# design.net
KiCad netlist of a schematic drawn in EasyEDA Pro
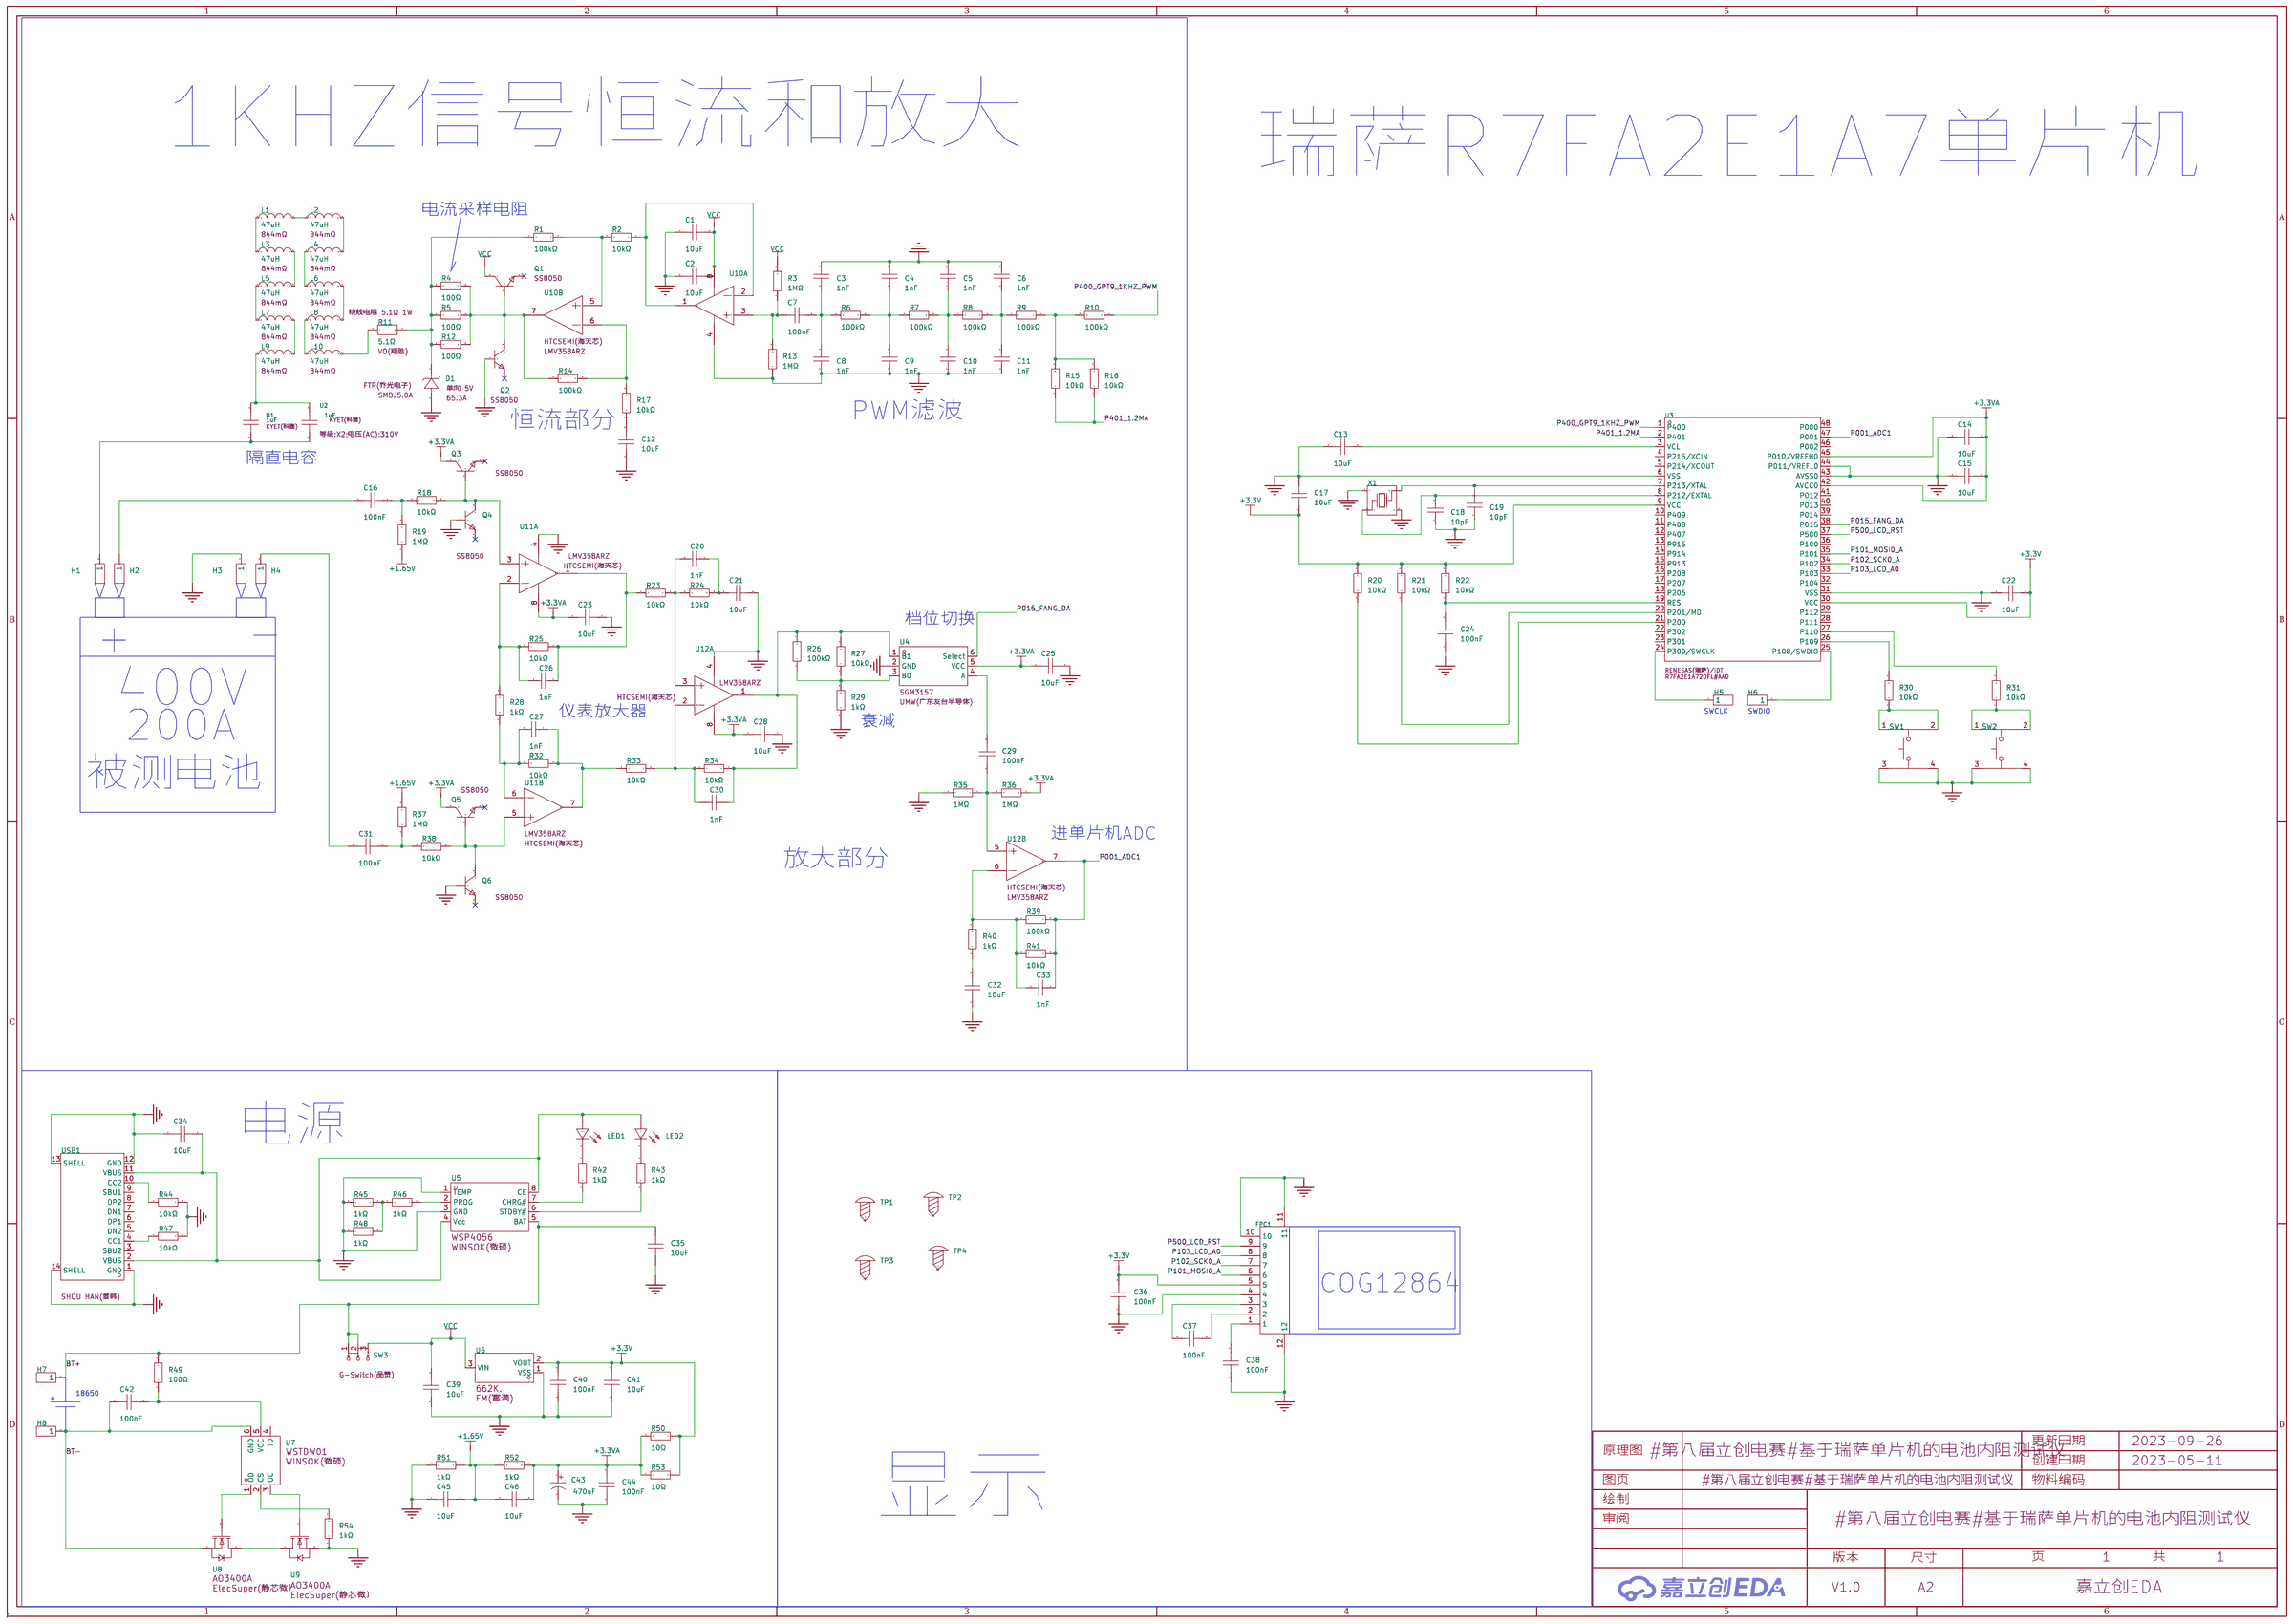
[diagram p0: schematic sheet]

(export (version "E")
  (design (tool "Eeschema 10.0.6"))
  (components
    (comp (ref "C1")
      (value "10uF")
      (footprint "easyedapro:C0603")
      (description "容值:10uF;精度:±10%;额定电压:10V;材质(温度系数):X5R;")
      (fields
        (field (name "Manufacturer Part") "CL10A106KP8NNNC")
        (field (name "Manufacturer") "SAMSUNG(三星)")
      )
      (libsource (lib "easyedapro") (part "CL10A106KP8NNNC"))
    )
    (comp (ref "C2")
      (value "10uF")
      (footprint "easyedapro:C0603")
      (description "容值:10uF;精度:±10%;额定电压:10V;材质(温度系数):X5R;")
      (fields
        (field (name "Manufacturer Part") "CL10A106KP8NNNC")
        (field (name "Manufacturer") "SAMSUNG(三星)")
      )
      (libsource (lib "easyedapro") (part "CL10A106KP8NNNC"))
    )
    (comp (ref "C3")
      (value "1nF")
      (footprint "easyedapro:C0603")
      (description "容值:1nF;精度:±5%;额定电压:50V;材质(温度系数):NP0;")
      (fields
        (field (name "Manufacturer Part") "CC0603JRNPO9BN102")
        (field (name "Manufacturer") "YAGEO(国巨)")
      )
      (libsource (lib "easyedapro") (part "CC0603JRNPO9BN102"))
    )
    (comp (ref "C4")
      (value "1nF")
      (footprint "easyedapro:C0603")
      (description "容值:1nF;精度:±5%;额定电压:50V;材质(温度系数):NP0;")
      (fields
        (field (name "Manufacturer Part") "CC0603JRNPO9BN102")
        (field (name "Manufacturer") "YAGEO(国巨)")
      )
      (libsource (lib "easyedapro") (part "CC0603JRNPO9BN102"))
    )
    (comp (ref "C5")
      (value "1nF")
      (footprint "easyedapro:C0603")
      (description "容值:1nF;精度:±5%;额定电压:50V;材质(温度系数):NP0;")
      (fields
        (field (name "Manufacturer Part") "CC0603JRNPO9BN102")
        (field (name "Manufacturer") "YAGEO(国巨)")
      )
      (libsource (lib "easyedapro") (part "CC0603JRNPO9BN102"))
    )
    (comp (ref "C6")
      (value "1nF")
      (footprint "easyedapro:C0603")
      (description "容值:1nF;精度:±5%;额定电压:50V;材质(温度系数):NP0;")
      (fields
        (field (name "Manufacturer Part") "CC0603JRNPO9BN102")
        (field (name "Manufacturer") "YAGEO(国巨)")
      )
      (libsource (lib "easyedapro") (part "CC0603JRNPO9BN102"))
    )
    (comp (ref "C7")
      (value "100nF")
      (footprint "easyedapro:C0603")
      (description "容值:100nF;精度:±10%;额定电压:50V;材质(温度系数):X7R;")
      (fields
        (field (name "Manufacturer Part") "CC0603KRX7R9BB104")
        (field (name "Manufacturer") "YAGEO(国巨)")
      )
      (libsource (lib "easyedapro") (part "CC0603KRX7R9BB104"))
    )
    (comp (ref "C8")
      (value "1nF")
      (footprint "easyedapro:C0603")
      (description "容值:1nF;精度:±5%;额定电压:50V;材质(温度系数):NP0;")
      (fields
        (field (name "Manufacturer Part") "CC0603JRNPO9BN102")
        (field (name "Manufacturer") "YAGEO(国巨)")
      )
      (libsource (lib "easyedapro") (part "CC0603JRNPO9BN102"))
    )
    (comp (ref "C9")
      (value "1nF")
      (footprint "easyedapro:C0603")
      (description "容值:1nF;精度:±5%;额定电压:50V;材质(温度系数):NP0;")
      (fields
        (field (name "Manufacturer Part") "CC0603JRNPO9BN102")
        (field (name "Manufacturer") "YAGEO(国巨)")
      )
      (libsource (lib "easyedapro") (part "CC0603JRNPO9BN102"))
    )
    (comp (ref "C10")
      (value "1nF")
      (footprint "easyedapro:C0603")
      (description "容值:1nF;精度:±5%;额定电压:50V;材质(温度系数):NP0;")
      (fields
        (field (name "Manufacturer Part") "CC0603JRNPO9BN102")
        (field (name "Manufacturer") "YAGEO(国巨)")
      )
      (libsource (lib "easyedapro") (part "CC0603JRNPO9BN102"))
    )
    (comp (ref "C11")
      (value "1nF")
      (footprint "easyedapro:C0603")
      (description "容值:1nF;精度:±5%;额定电压:50V;材质(温度系数):NP0;")
      (fields
        (field (name "Manufacturer Part") "CC0603JRNPO9BN102")
        (field (name "Manufacturer") "YAGEO(国巨)")
      )
      (libsource (lib "easyedapro") (part "CC0603JRNPO9BN102"))
    )
    (comp (ref "C12")
      (value "10uF")
      (footprint "easyedapro:C0603")
      (description "容值:10uF;精度:±10%;额定电压:10V;材质(温度系数):X5R;")
      (fields
        (field (name "Manufacturer Part") "CL10A106KP8NNNC")
        (field (name "Manufacturer") "SAMSUNG(三星)")
      )
      (libsource (lib "easyedapro") (part "CL10A106KP8NNNC"))
    )
    (comp (ref "C13")
      (value "10uF")
      (footprint "easyedapro:C0603")
      (description "容值:10uF;精度:±10%;额定电压:10V;材质(温度系数):X5R;")
      (fields
        (field (name "Manufacturer Part") "CL10A106KP8NNNC")
        (field (name "Manufacturer") "SAMSUNG(三星)")
      )
      (libsource (lib "easyedapro") (part "CL10A106KP8NNNC"))
    )
    (comp (ref "C14")
      (value "10uF")
      (footprint "easyedapro:C0603")
      (description "容值:10uF;精度:±10%;额定电压:10V;材质(温度系数):X5R;")
      (fields
        (field (name "Manufacturer Part") "CL10A106KP8NNNC")
        (field (name "Manufacturer") "SAMSUNG(三星)")
      )
      (libsource (lib "easyedapro") (part "CL10A106KP8NNNC"))
    )
    (comp (ref "C15")
      (value "10uF")
      (footprint "easyedapro:C0603")
      (description "容值:10uF;精度:±10%;额定电压:10V;材质(温度系数):X5R;")
      (fields
        (field (name "Manufacturer Part") "CL10A106KP8NNNC")
        (field (name "Manufacturer") "SAMSUNG(三星)")
      )
      (libsource (lib "easyedapro") (part "CL10A106KP8NNNC"))
    )
    (comp (ref "C16")
      (value "100nF")
      (footprint "easyedapro:CAP-TH_L13.0-W6.0-P10.00-D1.0")
      (description "等级:X2;容值:100nF;精度:±10%;")
      (fields (field (name "Manufacturer Part") "MP2104K27C3X6LC") (field (name "Manufacturer") "SRD(圣融达)"))
      (libsource (lib "easyedapro") (part "MP2104KGC3XLC"))
    )
    (comp (ref "C17")
      (value "10uF")
      (footprint "easyedapro:C0603")
      (description "容值:10uF;精度:±10%;额定电压:10V;材质(温度系数):X5R;")
      (fields
        (field (name "Manufacturer Part") "CL10A106KP8NNNC")
        (field (name "Manufacturer") "SAMSUNG(三星)")
      )
      (libsource (lib "easyedapro") (part "CL10A106KP8NNNC"))
    )
    (comp (ref "C18")
      (value "10pF")
      (footprint "easyedapro:C0603")
      (description "容值:10pF;精度:±5%;额定电压:50V;材质(温度系数):NP0;")
      (fields
        (field (name "Manufacturer Part") "CC0603JRNPO9BN100")
        (field (name "Manufacturer") "YAGEO(国巨)")
      )
      (libsource (lib "easyedapro") (part "CC0603JRNPO9BN100"))
    )
    (comp (ref "C19")
      (value "10pF")
      (footprint "easyedapro:C0603")
      (description "容值:10pF;精度:±5%;额定电压:50V;材质(温度系数):NP0;")
      (fields
        (field (name "Manufacturer Part") "CC0603JRNPO9BN100")
        (field (name "Manufacturer") "YAGEO(国巨)")
      )
      (libsource (lib "easyedapro") (part "CC0603JRNPO9BN100"))
    )
    (comp (ref "C20")
      (value "1nF")
      (footprint "easyedapro:C0603")
      (description "容值:1nF;精度:±5%;额定电压:50V;材质(温度系数):NP0;")
      (fields
        (field (name "Manufacturer Part") "CC0603JRNPO9BN102")
        (field (name "Manufacturer") "YAGEO(国巨)")
      )
      (libsource (lib "easyedapro") (part "CC0603JRNPO9BN102"))
    )
    (comp (ref "C21")
      (value "10uF")
      (footprint "easyedapro:C0603")
      (description "容值:10uF;精度:±10%;额定电压:10V;材质(温度系数):X5R;")
      (fields
        (field (name "Manufacturer Part") "CL10A106KP8NNNC")
        (field (name "Manufacturer") "SAMSUNG(三星)")
      )
      (libsource (lib "easyedapro") (part "CL10A106KP8NNNC"))
    )
    (comp (ref "C22")
      (value "10uF")
      (footprint "easyedapro:C0603")
      (description "容值:10uF;精度:±10%;额定电压:10V;材质(温度系数):X5R;")
      (fields
        (field (name "Manufacturer Part") "CL10A106KP8NNNC")
        (field (name "Manufacturer") "SAMSUNG(三星)")
      )
      (libsource (lib "easyedapro") (part "CL10A106KP8NNNC"))
    )
    (comp (ref "C23")
      (value "10uF")
      (footprint "easyedapro:C0603")
      (description "容值:10uF;精度:±10%;额定电压:10V;材质(温度系数):X5R;")
      (fields
        (field (name "Manufacturer Part") "CL10A106KP8NNNC")
        (field (name "Manufacturer") "SAMSUNG(三星)")
      )
      (libsource (lib "easyedapro") (part "CL10A106KP8NNNC"))
    )
    (comp (ref "C24")
      (value "100nF")
      (footprint "easyedapro:C0603")
      (description "容值:100nF;精度:±10%;额定电压:50V;材质(温度系数):X7R;")
      (fields
        (field (name "Manufacturer Part") "CC0603KRX7R9BB104")
        (field (name "Manufacturer") "YAGEO(国巨)")
      )
      (libsource (lib "easyedapro") (part "CC0603KRX7R9BB104"))
    )
    (comp (ref "C25")
      (value "10uF")
      (footprint "easyedapro:C0603")
      (description "容值:10uF;精度:±10%;额定电压:10V;材质(温度系数):X5R;")
      (fields
        (field (name "Manufacturer Part") "CL10A106KP8NNNC")
        (field (name "Manufacturer") "SAMSUNG(三星)")
      )
      (libsource (lib "easyedapro") (part "CL10A106KP8NNNC"))
    )
    (comp (ref "C26")
      (value "1nF")
      (footprint "easyedapro:C0603")
      (description "容值:1nF;精度:±5%;额定电压:50V;材质(温度系数):NP0;")
      (fields
        (field (name "Manufacturer Part") "CC0603JRNPO9BN102")
        (field (name "Manufacturer") "YAGEO(国巨)")
      )
      (libsource (lib "easyedapro") (part "CC0603JRNPO9BN102"))
    )
    (comp (ref "C27")
      (value "1nF")
      (footprint "easyedapro:C0603")
      (description "容值:1nF;精度:±5%;额定电压:50V;材质(温度系数):NP0;")
      (fields
        (field (name "Manufacturer Part") "CC0603JRNPO9BN102")
        (field (name "Manufacturer") "YAGEO(国巨)")
      )
      (libsource (lib "easyedapro") (part "CC0603JRNPO9BN102"))
    )
    (comp (ref "C28")
      (value "10uF")
      (footprint "easyedapro:C0603")
      (description "容值:10uF;精度:±10%;额定电压:10V;材质(温度系数):X5R;")
      (fields
        (field (name "Manufacturer Part") "CL10A106KP8NNNC")
        (field (name "Manufacturer") "SAMSUNG(三星)")
      )
      (libsource (lib "easyedapro") (part "CL10A106KP8NNNC"))
    )
    (comp (ref "C29")
      (value "100nF")
      (footprint "easyedapro:C0603")
      (description "容值:100nF;精度:±10%;额定电压:50V;材质(温度系数):X7R;")
      (fields
        (field (name "Manufacturer Part") "CC0603KRX7R9BB104")
        (field (name "Manufacturer") "YAGEO(国巨)")
      )
      (libsource (lib "easyedapro") (part "CC0603KRX7R9BB104"))
    )
    (comp (ref "C30")
      (value "1nF")
      (footprint "easyedapro:C0603")
      (description "容值:1nF;精度:±5%;额定电压:50V;材质(温度系数):NP0;")
      (fields
        (field (name "Manufacturer Part") "CC0603JRNPO9BN102")
        (field (name "Manufacturer") "YAGEO(国巨)")
      )
      (libsource (lib "easyedapro") (part "CC0603JRNPO9BN102"))
    )
    (comp (ref "C31")
      (value "100nF")
      (footprint "easyedapro:CAP-TH_L13.0-W6.0-P10.00-D1.0")
      (description "等级:X2;容值:100nF;精度:±10%;")
      (fields (field (name "Manufacturer Part") "MP2104K27C3X6LC") (field (name "Manufacturer") "SRD(圣融达)"))
      (libsource (lib "easyedapro") (part "MP2104KGC3XLC"))
    )
    (comp (ref "C32")
      (value "10uF")
      (footprint "easyedapro:C0603")
      (description "容值:10uF;精度:±10%;额定电压:10V;材质(温度系数):X5R;")
      (fields
        (field (name "Manufacturer Part") "CL10A106KP8NNNC")
        (field (name "Manufacturer") "SAMSUNG(三星)")
      )
      (libsource (lib "easyedapro") (part "CL10A106KP8NNNC"))
    )
    (comp (ref "C33")
      (value "1nF")
      (footprint "easyedapro:C0603")
      (description "容值:1nF;精度:±5%;额定电压:50V;材质(温度系数):NP0;")
      (fields
        (field (name "Manufacturer Part") "CC0603JRNPO9BN102")
        (field (name "Manufacturer") "YAGEO(国巨)")
      )
      (libsource (lib "easyedapro") (part "CC0603JRNPO9BN102"))
    )
    (comp (ref "C34")
      (value "10uF")
      (footprint "easyedapro:C0603")
      (description "容值:10uF;精度:±10%;额定电压:10V;材质(温度系数):X5R;")
      (fields
        (field (name "Manufacturer Part") "CL10A106KP8NNNC")
        (field (name "Manufacturer") "SAMSUNG(三星)")
      )
      (libsource (lib "easyedapro") (part "CL10A106KP8NNNC"))
    )
    (comp (ref "C35")
      (value "10uF")
      (footprint "easyedapro:C0603")
      (description "容值:10uF;精度:±10%;额定电压:10V;材质(温度系数):X5R;")
      (fields
        (field (name "Manufacturer Part") "CL10A106KP8NNNC")
        (field (name "Manufacturer") "SAMSUNG(三星)")
      )
      (libsource (lib "easyedapro") (part "CL10A106KP8NNNC"))
    )
    (comp (ref "C36")
      (value "100nF")
      (footprint "easyedapro:C0603")
      (description "容值:100nF;精度:±10%;额定电压:50V;材质(温度系数):X7R;")
      (fields
        (field (name "Manufacturer Part") "CC0603KRX7R9BB104")
        (field (name "Manufacturer") "YAGEO(国巨)")
      )
      (libsource (lib "easyedapro") (part "CC0603KRX7R9BB104"))
    )
    (comp (ref "C37")
      (value "100nF")
      (footprint "easyedapro:C0603")
      (description "容值:100nF;精度:±10%;额定电压:50V;材质(温度系数):X7R;")
      (fields
        (field (name "Manufacturer Part") "CC0603KRX7R9BB104")
        (field (name "Manufacturer") "YAGEO(国巨)")
      )
      (libsource (lib "easyedapro") (part "CC0603KRX7R9BB104"))
    )
    (comp (ref "C38")
      (value "100nF")
      (footprint "easyedapro:C0603")
      (description "容值:100nF;精度:±10%;额定电压:50V;材质(温度系数):X7R;")
      (fields
        (field (name "Manufacturer Part") "CC0603KRX7R9BB104")
        (field (name "Manufacturer") "YAGEO(国巨)")
      )
      (libsource (lib "easyedapro") (part "CC0603KRX7R9BB104"))
    )
    (comp (ref "C39")
      (value "10uF")
      (footprint "easyedapro:C0603")
      (description "容值:10uF;精度:±10%;额定电压:10V;材质(温度系数):X5R;")
      (fields
        (field (name "Manufacturer Part") "CL10A106KP8NNNC")
        (field (name "Manufacturer") "SAMSUNG(三星)")
      )
      (libsource (lib "easyedapro") (part "CL10A106KP8NNNC"))
    )
    (comp (ref "C40")
      (value "100nF")
      (footprint "easyedapro:C0603")
      (description "容值:100nF;精度:±10%;额定电压:50V;材质(温度系数):X7R;")
      (fields
        (field (name "Manufacturer Part") "CC0603KRX7R9BB104")
        (field (name "Manufacturer") "YAGEO(国巨)")
      )
      (libsource (lib "easyedapro") (part "CC0603KRX7R9BB104"))
    )
    (comp (ref "C41")
      (value "10uF")
      (footprint "easyedapro:C0603")
      (description "容值:10uF;精度:±10%;额定电压:10V;材质(温度系数):X5R;")
      (fields
        (field (name "Manufacturer Part") "CL10A106KP8NNNC")
        (field (name "Manufacturer") "SAMSUNG(三星)")
      )
      (libsource (lib "easyedapro") (part "CL10A106KP8NNNC"))
    )
    (comp (ref "C42")
      (value "100nF")
      (footprint "easyedapro:C0603")
      (description "容值:100nF;精度:±10%;额定电压:50V;材质(温度系数):X7R;")
      (fields
        (field (name "Manufacturer Part") "CC0603KRX7R9BB104")
        (field (name "Manufacturer") "YAGEO(国巨)")
      )
      (libsource (lib "easyedapro") (part "CC0603KRX7R9BB104"))
    )
    (comp (ref "C43")
      (value "470uF")
      (footprint "easyedapro:CAP-TH_BD8.0-P3.50-D0.6-FD")
      (description "容值:470uF;精度:±20%;额定电压:16V;")
      (fields
        (field (name "Manufacturer Part") "KM477M016F12RR0VH2FP0")
        (field (name "Manufacturer") "CX(承兴)")
      )
      (libsource (lib "easyedapro") (part "470uf16v"))
    )
    (comp (ref "C44")
      (value "100nF")
      (footprint "easyedapro:C0603")
      (description "容值:100nF;精度:±10%;额定电压:50V;材质(温度系数):X7R;")
      (fields
        (field (name "Manufacturer Part") "CC0603KRX7R9BB104")
        (field (name "Manufacturer") "YAGEO(国巨)")
      )
      (libsource (lib "easyedapro") (part "CC0603KRX7R9BB104"))
    )
    (comp (ref "C45")
      (value "10uF")
      (footprint "easyedapro:C0603")
      (description "容值:10uF;精度:±10%;额定电压:10V;材质(温度系数):X5R;")
      (fields
        (field (name "Manufacturer Part") "CL10A106KP8NNNC")
        (field (name "Manufacturer") "SAMSUNG(三星)")
      )
      (libsource (lib "easyedapro") (part "CL10A106KP8NNNC"))
    )
    (comp (ref "C46")
      (value "10uF")
      (footprint "easyedapro:C0603")
      (description "容值:10uF;精度:±10%;额定电压:10V;材质(温度系数):X5R;")
      (fields
        (field (name "Manufacturer Part") "CL10A106KP8NNNC")
        (field (name "Manufacturer") "SAMSUNG(三星)")
      )
      (libsource (lib "easyedapro") (part "CL10A106KP8NNNC"))
    )
    (comp (ref "D1")
      (value "SMBJ5.0A")
      (footprint "easyedapro:SMB_L4.3-W3.6-LS5.3-RD")
      (description "极性:单向;反向截止电压(Vrwm):5V;击穿电压(最小值):6.4V;峰值脉冲电流(Ipp)@10/1000s:65.3A;最大钳位电压:9.2V;")
      (fields
        (field (name "Manufacturer Part") "SMBJ5.0A")
        (field (name "Manufacturer") "FTR(乔光电子)")
        (field (name "LCSC Part Name") "单向 5V")
        (field (name "Peak Pulse Current (Ipp)@10/1000μs") "65.3A")
      )
      (libsource (lib "easyedapro") (part "SMBJ5.0A_C693503"))
    )
    (comp (ref "FPC1")
      (value "AFA01-S10FCA-00")
      (footprint "easyedapro:FPC-SMD_10P-P1.0_FGS-XJ-H2.0")
      (description "间距:1mm;触点数量:10;锁定特性:翻盖式;安装类型:卧贴;触点类型:下接;")
      (fields (field (name "Manufacturer") "JS(钜硕电子)"))
      (libsource (lib "easyedapro") (part "AFA01-S10FCA-00"))
    )
    (comp (ref "H1")
      (value "~")
      (footprint "easyedapro:HDR-TH_1P-V-M_XKB_X4611WV-01I-C28D40")
      (libsource (lib "easyedapro") (part "HDR_1x1"))
    )
    (comp (ref "H2")
      (value "~")
      (footprint "easyedapro:HDR-TH_1P-V-M_XKB_X4611WV-01I-C28D40")
      (libsource (lib "easyedapro") (part "HDR_1x1"))
    )
    (comp (ref "H3")
      (value "~")
      (footprint "easyedapro:HDR-TH_1P-V-M_XKB_X4611WV-01I-C28D40")
      (libsource (lib "easyedapro") (part "HDR_1x1"))
    )
    (comp (ref "H4")
      (value "~")
      (footprint "easyedapro:HDR-TH_1P-V-M_XKB_X4611WV-01I-C28D40")
      (libsource (lib "easyedapro") (part "HDR_1x1"))
    )
    (comp (ref "H5")
      (value "~")
      (footprint "easyedapro:HDR-TH_1P-V-M_XKB_X4611WV-01I-C28D40")
      (libsource (lib "easyedapro") (part "HDR_1x1"))
    )
    (comp (ref "H6")
      (value "~")
      (footprint "easyedapro:HDR-TH_1P-V-M_XKB_X4611WV-01I-C28D40")
      (libsource (lib "easyedapro") (part "HDR_1x1"))
    )
    (comp (ref "H7")
      (value "~")
      (footprint "easyedapro:HDR-TH_1P-V-M_XKB_X4611WV-01I-C28D40")
      (libsource (lib "easyedapro") (part "HDR_1x1"))
    )
    (comp (ref "H8")
      (value "~")
      (footprint "easyedapro:HDR-TH_1P-V-M_XKB_X4611WV-01I-C28D40")
      (libsource (lib "easyedapro") (part "HDR_1x1"))
    )
    (comp (ref "L1")
      (value "47uH")
      (footprint "easyedapro:IND-SMD_L4.5-W4.0_SLF0403")
      (description "电感值:47uH;精度:±10%;额定电流:540mA;")
      (fields
        (field (name "Manufacturer Part") "SLF0403-470KTT")
        (field (name "Manufacturer") "Sunltech(韩国顺磁)")
        (field (name "DC Resistance (DCR)") "844mΩ")
      )
      (libsource (lib "easyedapro") (part "SLF0403-470KTT"))
    )
    (comp (ref "L2")
      (value "47uH")
      (footprint "easyedapro:IND-SMD_L4.5-W4.0_SLF0403")
      (description "电感值:47uH;精度:±10%;额定电流:540mA;")
      (fields
        (field (name "Manufacturer Part") "SLF0403-470KTT")
        (field (name "Manufacturer") "Sunltech(韩国顺磁)")
        (field (name "DC Resistance (DCR)") "844mΩ")
      )
      (libsource (lib "easyedapro") (part "SLF0403-470KTT"))
    )
    (comp (ref "L3")
      (value "47uH")
      (footprint "easyedapro:IND-SMD_L4.5-W4.0_SLF0403")
      (description "电感值:47uH;精度:±10%;额定电流:540mA;")
      (fields
        (field (name "Manufacturer Part") "SLF0403-470KTT")
        (field (name "Manufacturer") "Sunltech(韩国顺磁)")
        (field (name "DC Resistance (DCR)") "844mΩ")
      )
      (libsource (lib "easyedapro") (part "SLF0403-470KTT"))
    )
    (comp (ref "L4")
      (value "47uH")
      (footprint "easyedapro:IND-SMD_L4.5-W4.0_SLF0403")
      (description "电感值:47uH;精度:±10%;额定电流:540mA;")
      (fields
        (field (name "Manufacturer Part") "SLF0403-470KTT")
        (field (name "Manufacturer") "Sunltech(韩国顺磁)")
        (field (name "DC Resistance (DCR)") "844mΩ")
      )
      (libsource (lib "easyedapro") (part "SLF0403-470KTT"))
    )
    (comp (ref "L5")
      (value "47uH")
      (footprint "easyedapro:IND-SMD_L4.5-W4.0_SLF0403")
      (description "电感值:47uH;精度:±10%;额定电流:540mA;")
      (fields
        (field (name "Manufacturer Part") "SLF0403-470KTT")
        (field (name "Manufacturer") "Sunltech(韩国顺磁)")
        (field (name "DC Resistance (DCR)") "844mΩ")
      )
      (libsource (lib "easyedapro") (part "SLF0403-470KTT"))
    )
    (comp (ref "L6")
      (value "47uH")
      (footprint "easyedapro:IND-SMD_L4.5-W4.0_SLF0403")
      (description "电感值:47uH;精度:±10%;额定电流:540mA;")
      (fields
        (field (name "Manufacturer Part") "SLF0403-470KTT")
        (field (name "Manufacturer") "Sunltech(韩国顺磁)")
        (field (name "DC Resistance (DCR)") "844mΩ")
      )
      (libsource (lib "easyedapro") (part "SLF0403-470KTT"))
    )
    (comp (ref "L7")
      (value "47uH")
      (footprint "easyedapro:IND-SMD_L4.5-W4.0_SLF0403")
      (description "电感值:47uH;精度:±10%;额定电流:540mA;")
      (fields
        (field (name "Manufacturer Part") "SLF0403-470KTT")
        (field (name "Manufacturer") "Sunltech(韩国顺磁)")
        (field (name "DC Resistance (DCR)") "844mΩ")
      )
      (libsource (lib "easyedapro") (part "SLF0403-470KTT"))
    )
    (comp (ref "L8")
      (value "47uH")
      (footprint "easyedapro:IND-SMD_L4.5-W4.0_SLF0403")
      (description "电感值:47uH;精度:±10%;额定电流:540mA;")
      (fields
        (field (name "Manufacturer Part") "SLF0403-470KTT")
        (field (name "Manufacturer") "Sunltech(韩国顺磁)")
        (field (name "DC Resistance (DCR)") "844mΩ")
      )
      (libsource (lib "easyedapro") (part "SLF0403-470KTT"))
    )
    (comp (ref "L9")
      (value "47uH")
      (footprint "easyedapro:IND-SMD_L4.5-W4.0_SLF0403")
      (description "电感值:47uH;精度:±10%;额定电流:540mA;")
      (fields
        (field (name "Manufacturer Part") "SLF0403-470KTT")
        (field (name "Manufacturer") "Sunltech(韩国顺磁)")
        (field (name "DC Resistance (DCR)") "844mΩ")
      )
      (libsource (lib "easyedapro") (part "SLF0403-470KTT"))
    )
    (comp (ref "L10")
      (value "47uH")
      (footprint "easyedapro:IND-SMD_L4.5-W4.0_SLF0403")
      (description "电感值:47uH;精度:±10%;额定电流:540mA;")
      (fields
        (field (name "Manufacturer Part") "SLF0403-470KTT")
        (field (name "Manufacturer") "Sunltech(韩国顺磁)")
        (field (name "DC Resistance (DCR)") "844mΩ")
      )
      (libsource (lib "easyedapro") (part "SLF0403-470KTT"))
    )
    (comp (ref "LED1")
      (value "204-10SURD/S530-A3-L")
      (footprint "easyedapro:LED-TH_BD3.0-P2.54-FD")
      (description "发光颜色:红灯;二极管配置:-;主波长:624nm;色温:-;功率:60mW;安装方式:-;")
      (fields (field (name "Manufacturer") "EVERLIGHT(亿光)"))
      (libsource (lib "easyedapro") (part "204-10SURD/S530-A3-L"))
    )
    (comp (ref "LED2")
      (value "204-10SURD/S530-A3-L")
      (footprint "easyedapro:LED-TH_BD3.0-P2.54-FD")
      (description "发光颜色:红灯;二极管配置:-;主波长:624nm;色温:-;功率:60mW;安装方式:-;")
      (fields (field (name "Manufacturer") "EVERLIGHT(亿光)"))
      (libsource (lib "easyedapro") (part "204-10SURD/S530-A3-L"))
    )
    (comp (ref "Q1")
      (value "SS8050")
      (footprint "easyedapro:SOT-23-3_L2.9-W1.3-P1.90-LS2.4-BR")
      (fields (field (name "Manufacturer Part") "SS8050") (field (name "Manufacturer") "ElecSuper(静芯微）"))
      (libsource (lib "easyedapro") (part "SS8050_C5249676"))
    )
    (comp (ref "Q2")
      (value "SS8050")
      (footprint "easyedapro:SOT-23-3_L2.9-W1.3-P1.90-LS2.4-BR")
      (fields (field (name "Manufacturer Part") "SS8050") (field (name "Manufacturer") "ElecSuper(静芯微）"))
      (libsource (lib "easyedapro") (part "SS8050_C5249676"))
    )
    (comp (ref "Q3")
      (value "SS8050")
      (footprint "easyedapro:SOT-23-3_L2.9-W1.3-P1.90-LS2.4-BR")
      (fields (field (name "Manufacturer Part") "SS8050") (field (name "Manufacturer") "ElecSuper(静芯微）"))
      (libsource (lib "easyedapro") (part "SS8050_C5249676"))
    )
    (comp (ref "Q4")
      (value "SS8050")
      (footprint "easyedapro:SOT-23-3_L2.9-W1.3-P1.90-LS2.4-BR")
      (fields (field (name "Manufacturer Part") "SS8050") (field (name "Manufacturer") "ElecSuper(静芯微）"))
      (libsource (lib "easyedapro") (part "SS8050_C5249676"))
    )
    (comp (ref "Q5")
      (value "SS8050")
      (footprint "easyedapro:SOT-23-3_L2.9-W1.3-P1.90-LS2.4-BR")
      (fields (field (name "Manufacturer Part") "SS8050") (field (name "Manufacturer") "ElecSuper(静芯微）"))
      (libsource (lib "easyedapro") (part "SS8050_C5249676"))
    )
    (comp (ref "Q6")
      (value "SS8050")
      (footprint "easyedapro:SOT-23-3_L2.9-W1.3-P1.90-LS2.4-BR")
      (fields (field (name "Manufacturer Part") "SS8050") (field (name "Manufacturer") "ElecSuper(静芯微）"))
      (libsource (lib "easyedapro") (part "SS8050_C5249676"))
    )
    (comp (ref "R1")
      (value "100kΩ")
      (footprint "easyedapro:R0603")
      (description "电阻类型:厚膜电阻;阻值:100kΩ;精度:±1%;功率:100mW;")
      (fields (field (name "Manufacturer Part") "RC0603FR-07100KL") (field (name "Manufacturer") "YAGEO(国巨)"))
      (libsource (lib "easyedapro") (part "RC0603FR-07100KL"))
    )
    (comp (ref "R2")
      (value "10kΩ")
      (footprint "easyedapro:R0603")
      (description "电阻类型:厚膜电阻;阻值:10kΩ;精度:±1%;功率:100mW;")
      (fields (field (name "Manufacturer Part") "RC0603FR-0710KL") (field (name "Manufacturer") "YAGEO(国巨)"))
      (libsource (lib "easyedapro") (part "RC0603FR-0710KL"))
    )
    (comp (ref "R3")
      (value "1MΩ")
      (footprint "easyedapro:R0603")
      (description "电阻类型:厚膜电阻;阻值:1MΩ;精度:±1%;功率:100mW;")
      (fields
        (field (name "Manufacturer Part") "0603WAF1004T5E")
        (field (name "Manufacturer") "UNI-ROYAL(厚声)")
      )
      (libsource (lib "easyedapro") (part "0603WAF1004T5E"))
    )
    (comp (ref "R4")
      (value "100Ω")
      (footprint "easyedapro:R2512")
      (description "电阻类型:厚膜电阻;阻值:100Ω;精度:±5%;功率:2W;")
      (fields
        (field (name "Manufacturer Part") "CRH2512J100RE04Z")
        (field (name "Manufacturer") "EVER OHMS(天二科技)")
      )
      (libsource (lib "easyedapro") (part "CR2512J100RE042W"))
    )
    (comp (ref "R5")
      (value "100Ω")
      (footprint "easyedapro:R2512")
      (description "电阻类型:厚膜电阻;阻值:100Ω;精度:±5%;功率:2W;")
      (fields
        (field (name "Manufacturer Part") "CRH2512J100RE04Z")
        (field (name "Manufacturer") "EVER OHMS(天二科技)")
      )
      (libsource (lib "easyedapro") (part "CR2512J100RE042W"))
    )
    (comp (ref "R6")
      (value "100kΩ")
      (footprint "easyedapro:R0603")
      (description "电阻类型:厚膜电阻;阻值:100kΩ;精度:±1%;功率:100mW;")
      (fields (field (name "Manufacturer Part") "RC0603FR-07100KL") (field (name "Manufacturer") "YAGEO(国巨)"))
      (libsource (lib "easyedapro") (part "RC0603FR-07100KL"))
    )
    (comp (ref "R7")
      (value "100kΩ")
      (footprint "easyedapro:R0603")
      (description "电阻类型:厚膜电阻;阻值:100kΩ;精度:±1%;功率:100mW;")
      (fields (field (name "Manufacturer Part") "RC0603FR-07100KL") (field (name "Manufacturer") "YAGEO(国巨)"))
      (libsource (lib "easyedapro") (part "RC0603FR-07100KL"))
    )
    (comp (ref "R8")
      (value "100kΩ")
      (footprint "easyedapro:R0603")
      (description "电阻类型:厚膜电阻;阻值:100kΩ;精度:±1%;功率:100mW;")
      (fields (field (name "Manufacturer Part") "RC0603FR-07100KL") (field (name "Manufacturer") "YAGEO(国巨)"))
      (libsource (lib "easyedapro") (part "RC0603FR-07100KL"))
    )
    (comp (ref "R9")
      (value "100kΩ")
      (footprint "easyedapro:R0603")
      (description "电阻类型:厚膜电阻;阻值:100kΩ;精度:±1%;功率:100mW;")
      (fields (field (name "Manufacturer Part") "RC0603FR-07100KL") (field (name "Manufacturer") "YAGEO(国巨)"))
      (libsource (lib "easyedapro") (part "RC0603FR-07100KL"))
    )
    (comp (ref "R10")
      (value "100kΩ")
      (footprint "easyedapro:R0603")
      (description "电阻类型:厚膜电阻;阻值:100kΩ;精度:±1%;功率:100mW;")
      (fields (field (name "Manufacturer Part") "RC0603FR-07100KL") (field (name "Manufacturer") "YAGEO(国巨)"))
      (libsource (lib "easyedapro") (part "RC0603FR-07100KL"))
    )
    (comp (ref "R11")
      (value "5.1Ω")
      (footprint "easyedapro:RES-TH_BD3.5-L9.0-P13.00-D0.8")
      (description "电阻类型:绕线电阻;阻值:5.1Ω;精度:±5%;功率:1W;温度系数:±350ppm/°C;")
      (fields
        (field (name "Manufacturer Part") "KNP1WS-5Ω1±5%-2T52")
        (field (name "Manufacturer") "VO(翔胜)")
        (field (name "LCSC Part Name") "绕线电阻 5.1Ω 1W")
      )
      (libsource (lib "easyedapro") (part "KNP1WS-5Ω1±5%-2T52"))
    )
    (comp (ref "R12")
      (value "100Ω")
      (footprint "easyedapro:R2512")
      (description "电阻类型:厚膜电阻;阻值:100Ω;精度:±5%;功率:2W;")
      (fields
        (field (name "Manufacturer Part") "CRH2512J100RE04Z")
        (field (name "Manufacturer") "EVER OHMS(天二科技)")
      )
      (libsource (lib "easyedapro") (part "CR2512J100RE042W"))
    )
    (comp (ref "R13")
      (value "1MΩ")
      (footprint "easyedapro:R0603")
      (description "电阻类型:厚膜电阻;阻值:1MΩ;精度:±1%;功率:100mW;")
      (fields
        (field (name "Manufacturer Part") "0603WAF1004T5E")
        (field (name "Manufacturer") "UNI-ROYAL(厚声)")
      )
      (libsource (lib "easyedapro") (part "0603WAF1004T5E"))
    )
    (comp (ref "R14")
      (value "100kΩ")
      (footprint "easyedapro:R0603")
      (description "电阻类型:厚膜电阻;阻值:100kΩ;精度:±1%;功率:100mW;")
      (fields (field (name "Manufacturer Part") "RC0603FR-07100KL") (field (name "Manufacturer") "YAGEO(国巨)"))
      (libsource (lib "easyedapro") (part "RC0603FR-07100KL"))
    )
    (comp (ref "R15")
      (value "10kΩ")
      (footprint "easyedapro:R0603")
      (description "电阻类型:厚膜电阻;阻值:10kΩ;精度:±1%;功率:100mW;")
      (fields (field (name "Manufacturer Part") "RC0603FR-0710KL") (field (name "Manufacturer") "YAGEO(国巨)"))
      (libsource (lib "easyedapro") (part "RC0603FR-0710KL"))
    )
    (comp (ref "R16")
      (value "10kΩ")
      (footprint "easyedapro:R0603")
      (description "电阻类型:厚膜电阻;阻值:10kΩ;精度:±1%;功率:100mW;")
      (fields (field (name "Manufacturer Part") "RC0603FR-0710KL") (field (name "Manufacturer") "YAGEO(国巨)"))
      (libsource (lib "easyedapro") (part "RC0603FR-0710KL"))
    )
    (comp (ref "R17")
      (value "10kΩ")
      (footprint "easyedapro:R0603")
      (description "电阻类型:厚膜电阻;阻值:10kΩ;精度:±1%;功率:100mW;")
      (fields (field (name "Manufacturer Part") "RC0603FR-0710KL") (field (name "Manufacturer") "YAGEO(国巨)"))
      (libsource (lib "easyedapro") (part "RC0603FR-0710KL"))
    )
    (comp (ref "R18")
      (value "10kΩ")
      (footprint "easyedapro:R0603")
      (description "电阻类型:厚膜电阻;阻值:10kΩ;精度:±1%;功率:100mW;")
      (fields (field (name "Manufacturer Part") "RC0603FR-0710KL") (field (name "Manufacturer") "YAGEO(国巨)"))
      (libsource (lib "easyedapro") (part "RC0603FR-0710KL"))
    )
    (comp (ref "R19")
      (value "1MΩ")
      (footprint "easyedapro:R0603")
      (description "电阻类型:厚膜电阻;阻值:1MΩ;精度:±1%;功率:100mW;")
      (fields
        (field (name "Manufacturer Part") "0603WAF1004T5E")
        (field (name "Manufacturer") "UNI-ROYAL(厚声)")
      )
      (libsource (lib "easyedapro") (part "0603WAF1004T5E"))
    )
    (comp (ref "R20")
      (value "10kΩ")
      (footprint "easyedapro:R0603")
      (description "电阻类型:厚膜电阻;阻值:10kΩ;精度:±1%;功率:100mW;")
      (fields (field (name "Manufacturer Part") "RC0603FR-0710KL") (field (name "Manufacturer") "YAGEO(国巨)"))
      (libsource (lib "easyedapro") (part "RC0603FR-0710KL"))
    )
    (comp (ref "R21")
      (value "10kΩ")
      (footprint "easyedapro:R0603")
      (description "电阻类型:厚膜电阻;阻值:10kΩ;精度:±1%;功率:100mW;")
      (fields (field (name "Manufacturer Part") "RC0603FR-0710KL") (field (name "Manufacturer") "YAGEO(国巨)"))
      (libsource (lib "easyedapro") (part "RC0603FR-0710KL"))
    )
    (comp (ref "R22")
      (value "10kΩ")
      (footprint "easyedapro:R0603")
      (description "电阻类型:厚膜电阻;阻值:10kΩ;精度:±1%;功率:100mW;")
      (fields (field (name "Manufacturer Part") "RC0603FR-0710KL") (field (name "Manufacturer") "YAGEO(国巨)"))
      (libsource (lib "easyedapro") (part "RC0603FR-0710KL"))
    )
    (comp (ref "R23")
      (value "10kΩ")
      (footprint "easyedapro:R0603")
      (description "电阻类型:厚膜电阻;阻值:10kΩ;精度:±1%;功率:100mW;")
      (fields (field (name "Manufacturer Part") "RC0603FR-0710KL") (field (name "Manufacturer") "YAGEO(国巨)"))
      (libsource (lib "easyedapro") (part "RC0603FR-0710KL"))
    )
    (comp (ref "R24")
      (value "10kΩ")
      (footprint "easyedapro:R0603")
      (description "电阻类型:厚膜电阻;阻值:10kΩ;精度:±1%;功率:100mW;")
      (fields (field (name "Manufacturer Part") "RC0603FR-0710KL") (field (name "Manufacturer") "YAGEO(国巨)"))
      (libsource (lib "easyedapro") (part "RC0603FR-0710KL"))
    )
    (comp (ref "R25")
      (value "10kΩ")
      (footprint "easyedapro:R0603")
      (description "电阻类型:厚膜电阻;阻值:10kΩ;精度:±1%;功率:100mW;")
      (fields (field (name "Manufacturer Part") "RC0603FR-0710KL") (field (name "Manufacturer") "YAGEO(国巨)"))
      (libsource (lib "easyedapro") (part "RC0603FR-0710KL"))
    )
    (comp (ref "R26")
      (value "100kΩ")
      (footprint "easyedapro:R0603")
      (description "电阻类型:厚膜电阻;阻值:100kΩ;精度:±1%;功率:100mW;")
      (fields (field (name "Manufacturer Part") "RC0603FR-07100KL") (field (name "Manufacturer") "YAGEO(国巨)"))
      (libsource (lib "easyedapro") (part "RC0603FR-07100KL"))
    )
    (comp (ref "R27")
      (value "10kΩ")
      (footprint "easyedapro:R0603")
      (description "电阻类型:厚膜电阻;阻值:10kΩ;精度:±1%;功率:100mW;")
      (fields (field (name "Manufacturer Part") "RC0603FR-0710KL") (field (name "Manufacturer") "YAGEO(国巨)"))
      (libsource (lib "easyedapro") (part "RC0603FR-0710KL"))
    )
    (comp (ref "R28")
      (value "1kΩ")
      (footprint "easyedapro:R0603")
      (description "电阻类型:厚膜电阻;阻值:1kΩ;精度:±1%;功率:100mW;")
      (fields (field (name "Manufacturer Part") "RC0603FR-071KL") (field (name "Manufacturer") "YAGEO(国巨)"))
      (libsource (lib "easyedapro") (part "RC0603FR-071KL"))
    )
    (comp (ref "R29")
      (value "1kΩ")
      (footprint "easyedapro:R0603")
      (description "电阻类型:厚膜电阻;阻值:1kΩ;精度:±1%;功率:100mW;")
      (fields (field (name "Manufacturer Part") "RC0603FR-071KL") (field (name "Manufacturer") "YAGEO(国巨)"))
      (libsource (lib "easyedapro") (part "RC0603FR-071KL"))
    )
    (comp (ref "R30")
      (value "10kΩ")
      (footprint "easyedapro:R0603")
      (description "电阻类型:厚膜电阻;阻值:10kΩ;精度:±1%;功率:100mW;")
      (fields (field (name "Manufacturer Part") "RC0603FR-0710KL") (field (name "Manufacturer") "YAGEO(国巨)"))
      (libsource (lib "easyedapro") (part "RC0603FR-0710KL"))
    )
    (comp (ref "R31")
      (value "10kΩ")
      (footprint "easyedapro:R0603")
      (description "电阻类型:厚膜电阻;阻值:10kΩ;精度:±1%;功率:100mW;")
      (fields (field (name "Manufacturer Part") "RC0603FR-0710KL") (field (name "Manufacturer") "YAGEO(国巨)"))
      (libsource (lib "easyedapro") (part "RC0603FR-0710KL"))
    )
    (comp (ref "R32")
      (value "10kΩ")
      (footprint "easyedapro:R0603")
      (description "电阻类型:厚膜电阻;阻值:10kΩ;精度:±1%;功率:100mW;")
      (fields (field (name "Manufacturer Part") "RC0603FR-0710KL") (field (name "Manufacturer") "YAGEO(国巨)"))
      (libsource (lib "easyedapro") (part "RC0603FR-0710KL"))
    )
    (comp (ref "R33")
      (value "10kΩ")
      (footprint "easyedapro:R0603")
      (description "电阻类型:厚膜电阻;阻值:10kΩ;精度:±1%;功率:100mW;")
      (fields (field (name "Manufacturer Part") "RC0603FR-0710KL") (field (name "Manufacturer") "YAGEO(国巨)"))
      (libsource (lib "easyedapro") (part "RC0603FR-0710KL"))
    )
    (comp (ref "R34")
      (value "10kΩ")
      (footprint "easyedapro:R0603")
      (description "电阻类型:厚膜电阻;阻值:10kΩ;精度:±1%;功率:100mW;")
      (fields (field (name "Manufacturer Part") "RC0603FR-0710KL") (field (name "Manufacturer") "YAGEO(国巨)"))
      (libsource (lib "easyedapro") (part "RC0603FR-0710KL"))
    )
    (comp (ref "R35")
      (value "1MΩ")
      (footprint "easyedapro:R0603")
      (description "电阻类型:厚膜电阻;阻值:1MΩ;精度:±1%;功率:100mW;")
      (fields
        (field (name "Manufacturer Part") "0603WAF1004T5E")
        (field (name "Manufacturer") "UNI-ROYAL(厚声)")
      )
      (libsource (lib "easyedapro") (part "0603WAF1004T5E"))
    )
    (comp (ref "R36")
      (value "1MΩ")
      (footprint "easyedapro:R0603")
      (description "电阻类型:厚膜电阻;阻值:1MΩ;精度:±1%;功率:100mW;")
      (fields
        (field (name "Manufacturer Part") "0603WAF1004T5E")
        (field (name "Manufacturer") "UNI-ROYAL(厚声)")
      )
      (libsource (lib "easyedapro") (part "0603WAF1004T5E"))
    )
    (comp (ref "R37")
      (value "1MΩ")
      (footprint "easyedapro:R0603")
      (description "电阻类型:厚膜电阻;阻值:1MΩ;精度:±1%;功率:100mW;")
      (fields
        (field (name "Manufacturer Part") "0603WAF1004T5E")
        (field (name "Manufacturer") "UNI-ROYAL(厚声)")
      )
      (libsource (lib "easyedapro") (part "0603WAF1004T5E"))
    )
    (comp (ref "R38")
      (value "10kΩ")
      (footprint "easyedapro:R0603")
      (description "电阻类型:厚膜电阻;阻值:10kΩ;精度:±1%;功率:100mW;")
      (fields (field (name "Manufacturer Part") "RC0603FR-0710KL") (field (name "Manufacturer") "YAGEO(国巨)"))
      (libsource (lib "easyedapro") (part "RC0603FR-0710KL"))
    )
    (comp (ref "R39")
      (value "100kΩ")
      (footprint "easyedapro:R0603")
      (description "电阻类型:厚膜电阻;阻值:100kΩ;精度:±1%;功率:100mW;")
      (fields (field (name "Manufacturer Part") "RC0603FR-07100KL") (field (name "Manufacturer") "YAGEO(国巨)"))
      (libsource (lib "easyedapro") (part "RC0603FR-07100KL"))
    )
    (comp (ref "R40")
      (value "1kΩ")
      (footprint "easyedapro:R0603")
      (description "电阻类型:厚膜电阻;阻值:1kΩ;精度:±1%;功率:100mW;")
      (fields (field (name "Manufacturer Part") "RC0603FR-071KL") (field (name "Manufacturer") "YAGEO(国巨)"))
      (libsource (lib "easyedapro") (part "RC0603FR-071KL"))
    )
    (comp (ref "R41")
      (value "10kΩ")
      (footprint "easyedapro:R0603")
      (description "电阻类型:厚膜电阻;阻值:10kΩ;精度:±1%;功率:100mW;")
      (fields (field (name "Manufacturer Part") "RC0603FR-0710KL") (field (name "Manufacturer") "YAGEO(国巨)"))
      (libsource (lib "easyedapro") (part "RC0603FR-0710KL"))
    )
    (comp (ref "R42")
      (value "1kΩ")
      (footprint "easyedapro:R0603")
      (description "电阻类型:厚膜电阻;阻值:1kΩ;精度:±1%;功率:100mW;")
      (fields (field (name "Manufacturer Part") "RC0603FR-071KL") (field (name "Manufacturer") "YAGEO(国巨)"))
      (libsource (lib "easyedapro") (part "RC0603FR-071KL"))
    )
    (comp (ref "R43")
      (value "1kΩ")
      (footprint "easyedapro:R0603")
      (description "电阻类型:厚膜电阻;阻值:1kΩ;精度:±1%;功率:100mW;")
      (fields (field (name "Manufacturer Part") "RC0603FR-071KL") (field (name "Manufacturer") "YAGEO(国巨)"))
      (libsource (lib "easyedapro") (part "RC0603FR-071KL"))
    )
    (comp (ref "R44")
      (value "10kΩ")
      (footprint "easyedapro:R0603")
      (description "电阻类型:厚膜电阻;阻值:10kΩ;精度:±1%;功率:100mW;")
      (fields (field (name "Manufacturer Part") "RC0603FR-0710KL") (field (name "Manufacturer") "YAGEO(国巨)"))
      (libsource (lib "easyedapro") (part "RC0603FR-0710KL"))
    )
    (comp (ref "R45")
      (value "1kΩ")
      (footprint "easyedapro:R0603")
      (description "电阻类型:厚膜电阻;阻值:1kΩ;精度:±1%;功率:100mW;")
      (fields (field (name "Manufacturer Part") "RC0603FR-071KL") (field (name "Manufacturer") "YAGEO(国巨)"))
      (libsource (lib "easyedapro") (part "RC0603FR-071KL"))
    )
    (comp (ref "R46")
      (value "1kΩ")
      (footprint "easyedapro:R0603")
      (description "电阻类型:厚膜电阻;阻值:1kΩ;精度:±1%;功率:100mW;")
      (fields (field (name "Manufacturer Part") "RC0603FR-071KL") (field (name "Manufacturer") "YAGEO(国巨)"))
      (libsource (lib "easyedapro") (part "RC0603FR-071KL"))
    )
    (comp (ref "R47")
      (value "10kΩ")
      (footprint "easyedapro:R0603")
      (description "电阻类型:厚膜电阻;阻值:10kΩ;精度:±1%;功率:100mW;")
      (fields (field (name "Manufacturer Part") "RC0603FR-0710KL") (field (name "Manufacturer") "YAGEO(国巨)"))
      (libsource (lib "easyedapro") (part "RC0603FR-0710KL"))
    )
    (comp (ref "R48")
      (value "1kΩ")
      (footprint "easyedapro:R0603")
      (description "电阻类型:厚膜电阻;阻值:1kΩ;精度:±1%;功率:100mW;")
      (fields (field (name "Manufacturer Part") "RC0603FR-071KL") (field (name "Manufacturer") "YAGEO(国巨)"))
      (libsource (lib "easyedapro") (part "RC0603FR-071KL"))
    )
    (comp (ref "R49")
      (value "100Ω")
      (footprint "easyedapro:R0603")
      (description "电阻类型:厚膜电阻;阻值:100Ω;精度:±1%;功率:100mW;")
      (fields (field (name "Manufacturer Part") "RC0603FR-07100RL") (field (name "Manufacturer") "YAGEO(国巨)"))
      (libsource (lib "easyedapro") (part "RC0603FR-07100RL"))
    )
    (comp (ref "R50")
      (value "10Ω")
      (footprint "easyedapro:R0603")
      (description "电阻类型:厚膜电阻;阻值:10Ω;精度:±1%;功率:100mW;")
      (fields
        (field (name "Manufacturer Part") "0603WAF100JT5E")
        (field (name "Manufacturer") "UNI-ROYAL(厚声)")
      )
      (libsource (lib "easyedapro") (part "0603WAF100JT5E"))
    )
    (comp (ref "R51")
      (value "1kΩ")
      (footprint "easyedapro:R0603")
      (description "电阻类型:厚膜电阻;阻值:1kΩ;精度:±1%;功率:100mW;")
      (fields (field (name "Manufacturer Part") "RC0603FR-071KL") (field (name "Manufacturer") "YAGEO(国巨)"))
      (libsource (lib "easyedapro") (part "RC0603FR-071KL"))
    )
    (comp (ref "R52")
      (value "1kΩ")
      (footprint "easyedapro:R0603")
      (description "电阻类型:厚膜电阻;阻值:1kΩ;精度:±1%;功率:100mW;")
      (fields (field (name "Manufacturer Part") "RC0603FR-071KL") (field (name "Manufacturer") "YAGEO(国巨)"))
      (libsource (lib "easyedapro") (part "RC0603FR-071KL"))
    )
    (comp (ref "R53")
      (value "10Ω")
      (footprint "easyedapro:R0603")
      (description "电阻类型:厚膜电阻;阻值:10Ω;精度:±1%;功率:100mW;")
      (fields
        (field (name "Manufacturer Part") "0603WAF100JT5E")
        (field (name "Manufacturer") "UNI-ROYAL(厚声)")
      )
      (libsource (lib "easyedapro") (part "0603WAF100JT5E"))
    )
    (comp (ref "R54")
      (value "1kΩ")
      (footprint "easyedapro:R0603")
      (description "电阻类型:厚膜电阻;阻值:1kΩ;精度:±1%;功率:100mW;")
      (fields (field (name "Manufacturer Part") "RC0603FR-071KL") (field (name "Manufacturer") "YAGEO(国巨)"))
      (libsource (lib "easyedapro") (part "RC0603FR-071KL"))
    )
    (comp (ref "SW1")
      (value "1TS005A-2500-5001")
      (footprint "easyedapro:SW-TH_4P-L6.0-W6.0-P3.90-LS6.5")
      (description "触点电流:50mA;额定电压(DC):12V;额定功率:0.6W;绝缘电阻:100MΩ;电路结构:单刀单掷;安装方式:直插;带灯:无;作用力:250gf@±50gf;机械寿命:7万次;带支架:否;")
      (fields (field (name "Manufacturer") "HYP(鸿源精密)"))
      (libsource (lib "easyedapro") (part "1TS005A-2500-5001"))
    )
    (comp (ref "SW2")
      (value "1TS005A-2500-5001")
      (footprint "easyedapro:SW-TH_4P-L6.0-W6.0-P3.90-LS6.5")
      (description "触点电流:50mA;额定电压(DC):12V;额定功率:0.6W;绝缘电阻:100MΩ;电路结构:单刀单掷;安装方式:直插;带灯:无;作用力:250gf@±50gf;机械寿命:7万次;带支架:否;")
      (fields (field (name "Manufacturer") "HYP(鸿源精密)"))
      (libsource (lib "easyedapro") (part "1TS005A-2500-5001"))
    )
    (comp (ref "SW3")
      (value "SS-12F20-G070")
      (footprint "easyedapro:SW-TH_G-SWITCH_SS-12F20-G070")
      (description "额定电流(DC):500mA;额定电压(DC):250V;电路结构:单刀双掷;安装方式:直插;机械寿命:-;开关颜色:黑色;")
      (fields (field (name "Manufacturer") "G-Switch(品赞)"))
      (libsource (lib "easyedapro") (part "SS-12F20-G070"))
    )
    (comp (ref "TP1") (value "~") (footprint "easyedapro:M2螺丝") (libsource (lib "easyedapro") (part "螺丝孔")))
    (comp (ref "TP2") (value "~") (footprint "easyedapro:M2螺丝") (libsource (lib "easyedapro") (part "螺丝孔")))
    (comp (ref "TP3") (value "~") (footprint "easyedapro:M2螺丝") (libsource (lib "easyedapro") (part "螺丝孔")))
    (comp (ref "TP4") (value "~") (footprint "easyedapro:M2螺丝") (libsource (lib "easyedapro") (part "螺丝孔")))
    (comp (ref "U1")
      (value "1uF")
      (footprint "easyedapro:CAP-TH_L18.0-W11.0-P15.00-D0.8")
      (description "等级:X2;容值:1uF;精度:±10%;电压(AC):310V；380V；350V;")
      (fields (field (name "Manufacturer Part") "PX105K2C1503") (field (name "Manufacturer") "KYET(科雅)"))
      (libsource (lib "easyedapro") (part "PX105K2C1503"))
    )
    (comp (ref "U2")
      (value "1uF")
      (footprint "easyedapro:CAP-TH_L18.0-W11.0-P15.00-D0.8")
      (description "等级:X2;电压(AC):310V")
      (fields (field (name "Manufacturer Part") "PX105K2C1503") (field (name "Manufacturer") "KYET(科雅)"))
      (libsource (lib "easyedapro") (part "PX105K2C1503"))
    )
    (comp (ref "U3")
      (value "R7FA2E1A72DFL#AA0")
      (footprint "easyedapro:LQFP-48_L7.0-W7.0-P0.50-LS9.0-BL")
      (description "CPU内核:ARM Cortex-M23;CPU最大主频:48MHz;工作电压范围:1.6V~5.5V;程序存储容量:64KB;RAM总容量:16KB;GPIO端口数量:40;")
      (fields
        (field (name "Manufacturer Part") "R7FA2E1A72DFL#AA0")
        (field (name "Manufacturer") "RENESAS(瑞萨)/IDT")
      )
      (libsource (lib "easyedapro") (part "R7FA2E1A72DFL#AA0"))
    )
    (comp (ref "U4")
      (value "SGM3157")
      (footprint "easyedapro:SC-70-6_L2.2-W1.3-P0.65-LS2.1-BL")
      (description "开关电路:-;")
      (fields (field (name "Manufacturer Part") "SGM3157") (field (name "Manufacturer") "UMW(广东友台半导体)"))
      (libsource (lib "easyedapro") (part "SGM3157"))
    )
    (comp (ref "U5")
      (value "WSP4056")
      (footprint "easyedapro:SOP-8_L5.1-W3.9-P1.27-LS6.0-BL")
      (fields (field (name "Manufacturer Part") "WSP4056") (field (name "Manufacturer") "WINSOK(微硕)"))
      (libsource (lib "easyedapro") (part "WSP4056"))
    )
    (comp (ref "U6")
      (value "662K.")
      (footprint "easyedapro:SOT-23-3_L2.9-W1.3-P1.90-LS2.4-BR")
      (description "输出类型:-;")
      (fields (field (name "Manufacturer Part") "662K.") (field (name "Manufacturer") "FM(富满)"))
      (libsource (lib "easyedapro") (part "662K."))
    )
    (comp (ref "U7")
      (value "WSTDW01")
      (footprint "easyedapro:SOT-23-6_L2.9-W1.6-P0.95-LS2.8-BR")
      (description "充电电池的类型:-;电池单元组数:-;最大充电电流:-;充满的电池组电压:-;最大供应电压:-;")
      (fields (field (name "Manufacturer Part") "WSTDW01") (field (name "Manufacturer") "WINSOK(微硕)"))
      (libsource (lib "easyedapro") (part "WSTDW01"))
    )
    (comp (ref "U8")
      (value "AO3400A")
      (footprint "easyedapro:SOT-23-3_L3.0-W1.6-P1.90-LS2.8-BR")
      (description "类型:N沟道;漏源电压(Vdss):30V;连续漏极电流(Id):6A;功率(Pd):1.4W;导通电阻(RDS(on)@Vgs,Id):19mΩ@10V,6.0A;")
      (fields (field (name "Manufacturer Part") "AO3400A") (field (name "Manufacturer") "ElecSuper(静芯微）"))
      (libsource (lib "easyedapro") (part "AO3400A_C5224194"))
    )
    (comp (ref "U9")
      (value "AO3400A")
      (footprint "easyedapro:SOT-23-3_L3.0-W1.6-P1.90-LS2.8-BR")
      (description "类型:N沟道;漏源电压(Vdss):30V;连续漏极电流(Id):6A;功率(Pd):1.4W;导通电阻(RDS(on)@Vgs,Id):19mΩ@10V,6.0A;")
      (fields (field (name "Manufacturer Part") "AO3400A") (field (name "Manufacturer") "ElecSuper(静芯微）"))
      (libsource (lib "easyedapro") (part "AO3400A_C5224194"))
    )
    (comp (ref "U10")
      (value "LMV358ARZ")
      (footprint "easyedapro:SOP-8_L4.9-W3.9-P1.27-LS6.0-BL")
      (description "CMOS低功耗双路运算放大器")
      (fields (field (name "Manufacturer Part") "LMV358ARZ") (field (name "Manufacturer") "HTCSEMI(海天芯)"))
      (libsource (lib "easyedapro") (part "LMV358ARZ"))
    )
    (comp (ref "U11")
      (value "LMV358ARZ")
      (footprint "easyedapro:SOP-8_L4.9-W3.9-P1.27-LS6.0-BL")
      (description "CMOS低功耗双路运算放大器")
      (fields (field (name "Manufacturer Part") "LMV358ARZ") (field (name "Manufacturer") "HTCSEMI(海天芯)"))
      (libsource (lib "easyedapro") (part "LMV358ARZ"))
    )
    (comp (ref "U12")
      (value "LMV358ARZ")
      (footprint "easyedapro:SOP-8_L4.9-W3.9-P1.27-LS6.0-BL")
      (description "CMOS低功耗双路运算放大器")
      (fields (field (name "Manufacturer Part") "LMV358ARZ") (field (name "Manufacturer") "HTCSEMI(海天芯)"))
      (libsource (lib "easyedapro") (part "LMV358ARZ"))
    )
    (comp (ref "USB1")
      (value "TYPE-C 16PIN 2MD(073)")
      (footprint "easyedapro:USB-C-SMD_TYPE-C-6PIN-2MD-073")
      (description "连接器类型:Type-C;标准:-;公母:母座;触点数量:16;端口数量:1;安装方式:卧贴;额定电流 - 电源:5A;工作温度范围:-25°C~+85°C;")
      (fields (field (name "Manufacturer") "SHOU HAN(首韩)"))
      (libsource (lib "easyedapro") (part "TYPE-C 16PIN 2MD(073)"))
    )
    (comp (ref "X1")
      (value "-")
      (footprint "easyedapro:OSC-SMD_4P-L3.2-W2.5-BL")
      (description "频率:-;负载电容:-;")
      (fields (field (name "Manufacturer Part") "7325-3200A0910-00") (field (name "Manufacturer") "XTY(新天源)"))
      (libsource (lib "easyedapro") (part "7325-3200A0910-00"))
    )
  )
  (nets
    (net (code "1") (name "+1.65V") (class "Default")
      (node (ref "C45") (pin "2") (pinfunction "2_2") (pintype "input"))
      (node (ref "C46") (pin "1") (pinfunction "1_1") (pintype "input"))
      (node (ref "R19") (pin "1") (pinfunction "1_1") (pintype "input"))
      (node (ref "R37") (pin "2") (pinfunction "2_2") (pintype "input"))
      (node (ref "R51") (pin "1") (pinfunction "1_1") (pintype "input"))
      (node (ref "R52") (pin "2") (pinfunction "2_2") (pintype "input"))
    )
    (net (code "2") (name "+3.3V") (class "Default")
      (node (ref "C17") (pin "1") (pinfunction "1_1") (pintype "input"))
      (node (ref "C22") (pin "2") (pinfunction "2_2") (pintype "input"))
      (node (ref "C36") (pin "2") (pinfunction "2_2") (pintype "input"))
      (node (ref "C40") (pin "2") (pinfunction "2_2") (pintype "input"))
      (node (ref "C41") (pin "2") (pinfunction "2_2") (pintype "input"))
      (node (ref "FPC1") (pin "5") (pinfunction "5_5") (pintype "input"))
      (node (ref "R20") (pin "2") (pinfunction "2_2") (pintype "input"))
      (node (ref "R21") (pin "2") (pinfunction "2_2") (pintype "input"))
      (node (ref "R22") (pin "2") (pinfunction "2_2") (pintype "input"))
      (node (ref "R50") (pin "2") (pinfunction "2_2") (pintype "input"))
      (node (ref "R53") (pin "2") (pinfunction "2_2") (pintype "input"))
      (node (ref "U3") (pin "30") (pinfunction "VCC_30") (pintype "input"))
      (node (ref "U3") (pin "9") (pinfunction "VCC_9") (pintype "input"))
      (node (ref "U6") (pin "2") (pinfunction "VOUT_2") (pintype "input"))
    )
    (net (code "3") (name "+3.3VA") (class "Default")
      (node (ref "C14") (pin "1") (pinfunction "1_1") (pintype "input"))
      (node (ref "C15") (pin "2") (pinfunction "2_2") (pintype "input"))
      (node (ref "C23") (pin "1") (pinfunction "1_1") (pintype "input"))
      (node (ref "C25") (pin "1") (pinfunction "1_1") (pintype "input"))
      (node (ref "C28") (pin "1") (pinfunction "1_1") (pintype "input"))
      (node (ref "C43") (pin "1") (pinfunction "1_1") (pintype "input"))
      (node (ref "C44") (pin "2") (pinfunction "2_2") (pintype "input"))
      (node (ref "C46") (pin "2") (pinfunction "2_2") (pintype "input"))
      (node (ref "Q3") (pin "3") (pinfunction "C_3") (pintype "input"))
      (node (ref "Q5") (pin "3") (pinfunction "C_3") (pintype "input"))
      (node (ref "R36") (pin "1") (pinfunction "1_1") (pintype "input"))
      (node (ref "R50") (pin "1") (pinfunction "1_1") (pintype "input"))
      (node (ref "R52") (pin "1") (pinfunction "1_1") (pintype "input"))
      (node (ref "R53") (pin "1") (pinfunction "1_1") (pintype "input"))
      (node (ref "U11") (pin "8") (pinfunction "VCC_8") (pintype "input"))
      (node (ref "U12") (pin "8") (pinfunction "VCC_8") (pintype "input"))
      (node (ref "U3") (pin "42") (pinfunction "AVCC0_42") (pintype "input"))
      (node (ref "U3") (pin "45") (pinfunction "P010/VREFH0_45") (pintype "input"))
      (node (ref "U4") (pin "5") (pinfunction "VCC_5") (pintype "input"))
    )
    (net (code "4") (name "/BT+") (class "Default")
      (node (ref "C35") (pin "2") (pinfunction "2_2") (pintype "input"))
      (node (ref "H7") (pin "1") (pinfunction "1_1") (pintype "unspecified"))
      (node (ref "R49") (pin "2") (pinfunction "2_2") (pintype "input"))
      (node (ref "SW3") (pin "1") (pinfunction "1_1") (pintype "input"))
      (node (ref "SW3") (pin "2") (pinfunction "2_2") (pintype "input"))
      (node (ref "U5") (pin "5") (pinfunction "BAT_5") (pintype "input"))
    )
    (net (code "5") (name "/BT-") (class "Default")
      (node (ref "C42") (pin "1") (pinfunction "1_1") (pintype "input"))
      (node (ref "H8") (pin "1") (pinfunction "1_1") (pintype "unspecified"))
      (node (ref "U7") (pin "6") (pinfunction "GND_6") (pintype "input"))
      (node (ref "U8") (pin "2") (pinfunction "S_2") (pintype "input"))
    )
    (net (code "6") (name "/P001_ADC1") (class "Default")
      (node (ref "C33") (pin "1") (pinfunction "1_1") (pintype "input"))
      (node (ref "R39") (pin "2") (pinfunction "2_2") (pintype "input"))
      (node (ref "R41") (pin "2") (pinfunction "2_2") (pintype "input"))
      (node (ref "U12") (pin "7") (pinfunction "OUT2_7") (pintype "output"))
      (node (ref "U3") (pin "47") (pinfunction "P001_47") (pintype "input"))
    )
    (net (code "7") (name "/P015_FANG_DA") (class "Default")
      (node (ref "U3") (pin "38") (pinfunction "P015_38") (pintype "input"))
      (node (ref "U4") (pin "6") (pinfunction "Select_6") (pintype "input"))
    )
    (net (code "8") (name "/P101_MOSI0_A") (class "Default")
      (node (ref "FPC1") (pin "6") (pinfunction "6_6") (pintype "input"))
      (node (ref "U3") (pin "35") (pinfunction "P101_35") (pintype "input"))
    )
    (net (code "9") (name "/P102_SCK0_A") (class "Default")
      (node (ref "FPC1") (pin "7") (pinfunction "7_7") (pintype "input"))
      (node (ref "U3") (pin "34") (pinfunction "P102_34") (pintype "input"))
    )
    (net (code "10") (name "/P103_LCD_A0") (class "Default")
      (node (ref "FPC1") (pin "8") (pinfunction "8_8") (pintype "input"))
      (node (ref "U3") (pin "33") (pinfunction "P103_33") (pintype "input"))
    )
    (net (code "11") (name "/P400_GPT9_1KHZ_PWM") (class "Default")
      (node (ref "R10") (pin "2") (pinfunction "2_2") (pintype "input"))
      (node (ref "U3") (pin "1") (pinfunction "P400_1") (pintype "input"))
    )
    (net (code "12") (name "/P401_1.2MA") (class "Default")
      (node (ref "R15") (pin "1") (pinfunction "1_1") (pintype "input"))
      (node (ref "R16") (pin "1") (pinfunction "1_1") (pintype "input"))
      (node (ref "U3") (pin "2") (pinfunction "P401_2") (pintype "input"))
    )
    (net (code "13") (name "/P500_LCD_RST") (class "Default")
      (node (ref "FPC1") (pin "9") (pinfunction "9_9") (pintype "input"))
      (node (ref "U3") (pin "37") (pinfunction "P500_37") (pintype "input"))
    )
    (net (code "14") (name "GND") (class "Default")
      (node (ref "C1") (pin "1") (pinfunction "1_1") (pintype "input"))
      (node (ref "C10") (pin "1") (pinfunction "1_1") (pintype "input"))
      (node (ref "C11") (pin "1") (pinfunction "1_1") (pintype "input"))
      (node (ref "C12") (pin "1") (pinfunction "1_1") (pintype "input"))
      (node (ref "C13") (pin "1") (pinfunction "1_1") (pintype "input"))
      (node (ref "C14") (pin "2") (pinfunction "2_2") (pintype "input"))
      (node (ref "C15") (pin "1") (pinfunction "1_1") (pintype "input"))
      (node (ref "C17") (pin "2") (pinfunction "2_2") (pintype "input"))
      (node (ref "C18") (pin "1") (pinfunction "1_1") (pintype "input"))
      (node (ref "C19") (pin "1") (pinfunction "1_1") (pintype "input"))
      (node (ref "C2") (pin "1") (pinfunction "1_1") (pintype "input"))
      (node (ref "C21") (pin "2") (pinfunction "2_2") (pintype "input"))
      (node (ref "C22") (pin "1") (pinfunction "1_1") (pintype "input"))
      (node (ref "C23") (pin "2") (pinfunction "2_2") (pintype "input"))
      (node (ref "C24") (pin "1") (pinfunction "1_1") (pintype "input"))
      (node (ref "C25") (pin "2") (pinfunction "2_2") (pintype "input"))
      (node (ref "C28") (pin "2") (pinfunction "2_2") (pintype "input"))
      (node (ref "C3") (pin "2") (pinfunction "2_2") (pintype "input"))
      (node (ref "C32") (pin "1") (pinfunction "1_1") (pintype "input"))
      (node (ref "C34") (pin "1") (pinfunction "1_1") (pintype "input"))
      (node (ref "C35") (pin "1") (pinfunction "1_1") (pintype "input"))
      (node (ref "C36") (pin "1") (pinfunction "1_1") (pintype "input"))
      (node (ref "C38") (pin "1") (pinfunction "1_1") (pintype "input"))
      (node (ref "C39") (pin "1") (pinfunction "1_1") (pintype "input"))
      (node (ref "C4") (pin "2") (pinfunction "2_2") (pintype "input"))
      (node (ref "C40") (pin "1") (pinfunction "1_1") (pintype "input"))
      (node (ref "C41") (pin "1") (pinfunction "1_1") (pintype "input"))
      (node (ref "C43") (pin "2") (pinfunction "2_2") (pintype "input"))
      (node (ref "C44") (pin "1") (pinfunction "1_1") (pintype "input"))
      (node (ref "C45") (pin "1") (pinfunction "1_1") (pintype "input"))
      (node (ref "C5") (pin "2") (pinfunction "2_2") (pintype "input"))
      (node (ref "C6") (pin "2") (pinfunction "2_2") (pintype "input"))
      (node (ref "C8") (pin "1") (pinfunction "1_1") (pintype "input"))
      (node (ref "C9") (pin "1") (pinfunction "1_1") (pintype "input"))
      (node (ref "D1") (pin "2") (pinfunction "A_2") (pintype "input"))
      (node (ref "FPC1") (pin "10") (pinfunction "10_10") (pintype "input"))
      (node (ref "FPC1") (pin "11") (pinfunction "11_11") (pintype "input"))
      (node (ref "FPC1") (pin "12") (pinfunction "12_12") (pintype "input"))
      (node (ref "FPC1") (pin "4") (pinfunction "4_4") (pintype "input"))
      (node (ref "H3") (pin "1") (pinfunction "1_1") (pintype "unspecified"))
      (node (ref "Q2") (pin "1") (pinfunction "B_1") (pintype "input"))
      (node (ref "Q4") (pin "1") (pinfunction "B_1") (pintype "input"))
      (node (ref "Q6") (pin "1") (pinfunction "B_1") (pintype "input"))
      (node (ref "R13") (pin "1") (pinfunction "1_1") (pintype "input"))
      (node (ref "R29") (pin "1") (pinfunction "1_1") (pintype "input"))
      (node (ref "R35") (pin "2") (pinfunction "2_2") (pintype "input"))
      (node (ref "R44") (pin "2") (pinfunction "2_2") (pintype "input"))
      (node (ref "R45") (pin "2") (pinfunction "2_2") (pintype "input"))
      (node (ref "R47") (pin "2") (pinfunction "2_2") (pintype "input"))
      (node (ref "R48") (pin "2") (pinfunction "2_2") (pintype "input"))
      (node (ref "R51") (pin "2") (pinfunction "2_2") (pintype "input"))
      (node (ref "R54") (pin "1") (pinfunction "1_1") (pintype "input"))
      (node (ref "SW1") (pin "3") (pinfunction "3_3") (pintype "input"))
      (node (ref "SW1") (pin "4") (pinfunction "4_4") (pintype "input"))
      (node (ref "SW2") (pin "3") (pinfunction "3_3") (pintype "input"))
      (node (ref "SW2") (pin "4") (pinfunction "4_4") (pintype "input"))
      (node (ref "U10") (pin "4") (pinfunction "GND_4") (pintype "input"))
      (node (ref "U11") (pin "4") (pinfunction "GND_4") (pintype "input"))
      (node (ref "U12") (pin "4") (pinfunction "GND_4") (pintype "input"))
      (node (ref "U3") (pin "31") (pinfunction "VSS_31") (pintype "input"))
      (node (ref "U3") (pin "43") (pinfunction "AVSS0_43") (pintype "input"))
      (node (ref "U3") (pin "44") (pinfunction "P011/VREFL0_44") (pintype "input"))
      (node (ref "U3") (pin "6") (pinfunction "VSS_6") (pintype "input"))
      (node (ref "U4") (pin "2") (pinfunction "GND_2") (pintype "input"))
      (node (ref "U5") (pin "1") (pinfunction "TEMP_1") (pintype "input"))
      (node (ref "U5") (pin "3") (pinfunction "GND_3") (pintype "input"))
      (node (ref "U6") (pin "1") (pinfunction "VSS_1") (pintype "input"))
      (node (ref "U9") (pin "2") (pinfunction "S_2") (pintype "input"))
      (node (ref "USB1") (pin "1") (pinfunction "GND_1") (pintype "input"))
      (node (ref "USB1") (pin "12") (pinfunction "GND_12") (pintype "input"))
      (node (ref "USB1") (pin "13") (pinfunction "SHELL_13") (pintype "input"))
      (node (ref "USB1") (pin "14") (pinfunction "SHELL_14") (pintype "input"))
      (node (ref "X1") (pin "2") (pinfunction "2_2") (pintype "input"))
      (node (ref "X1") (pin "4") (pinfunction "4_4") (pintype "input"))
    )
    (net (code "15") (name "Net-(C3-Pad1)") (class "Default")
      (node (ref "C3") (pin "1") (pinfunction "1_1") (pintype "input"))
      (node (ref "C7") (pin "2") (pinfunction "2_2") (pintype "input"))
      (node (ref "C8") (pin "2") (pinfunction "2_2") (pintype "input"))
      (node (ref "R6") (pin "1") (pinfunction "1_1") (pintype "input"))
    )
    (net (code "16") (name "Net-(C4-Pad1)") (class "Default")
      (node (ref "C4") (pin "1") (pinfunction "1_1") (pintype "input"))
      (node (ref "C9") (pin "2") (pinfunction "2_2") (pintype "input"))
      (node (ref "R6") (pin "2") (pinfunction "2_2") (pintype "input"))
      (node (ref "R7") (pin "1") (pinfunction "1_1") (pintype "input"))
    )
    (net (code "17") (name "Net-(C10-Pad2)") (class "Default")
      (node (ref "C10") (pin "2") (pinfunction "2_2") (pintype "input"))
      (node (ref "C5") (pin "1") (pinfunction "1_1") (pintype "input"))
      (node (ref "R7") (pin "2") (pinfunction "2_2") (pintype "input"))
      (node (ref "R8") (pin "1") (pinfunction "1_1") (pintype "input"))
    )
    (net (code "18") (name "Net-(C11-Pad2)") (class "Default")
      (node (ref "C11") (pin "2") (pinfunction "2_2") (pintype "input"))
      (node (ref "C6") (pin "1") (pinfunction "1_1") (pintype "input"))
      (node (ref "R8") (pin "2") (pinfunction "2_2") (pintype "input"))
      (node (ref "R9") (pin "1") (pinfunction "1_1") (pintype "input"))
    )
    (net (code "19") (name "Net-(C12-Pad2)") (class "Default")
      (node (ref "C12") (pin "2") (pinfunction "2_2") (pintype "input"))
      (node (ref "R17") (pin "1") (pinfunction "1_1") (pintype "input"))
    )
    (net (code "20") (name "Net-(C16-Pad1)") (class "Default")
      (node (ref "C16") (pin "1") (pinfunction "1_1") (pintype "input"))
      (node (ref "R18") (pin "1") (pinfunction "1_1") (pintype "input"))
      (node (ref "R19") (pin "2") (pinfunction "2_2") (pintype "input"))
    )
    (net (code "21") (name "Net-(C16-Pad2)") (class "Default")
      (node (ref "C16") (pin "2") (pinfunction "2_2") (pintype "input"))
      (node (ref "H2") (pin "1") (pinfunction "1_1") (pintype "unspecified"))
    )
    (net (code "22") (name "Net-(C20-Pad1)") (class "Default")
      (node (ref "C20") (pin "1") (pinfunction "1_1") (pintype "input"))
      (node (ref "C21") (pin "1") (pinfunction "1_1") (pintype "input"))
      (node (ref "R24") (pin "2") (pinfunction "2_2") (pintype "input"))
    )
    (net (code "23") (name "Net-(C31-Pad1)") (class "Default")
      (node (ref "C31") (pin "1") (pinfunction "1_1") (pintype "input"))
      (node (ref "R37") (pin "1") (pinfunction "1_1") (pintype "input"))
      (node (ref "R38") (pin "1") (pinfunction "1_1") (pintype "input"))
    )
    (net (code "24") (name "Net-(C31-Pad2)") (class "Default")
      (node (ref "C31") (pin "2") (pinfunction "2_2") (pintype "input"))
      (node (ref "H4") (pin "1") (pinfunction "1_1") (pintype "unspecified"))
    )
    (net (code "25") (name "Net-(C32-Pad2)") (class "Default")
      (node (ref "C32") (pin "2") (pinfunction "2_2") (pintype "input"))
      (node (ref "R40") (pin "1") (pinfunction "1_1") (pintype "input"))
    )
    (net (code "26") (name "Net-(C37-Pad1)") (class "Default")
      (node (ref "C37") (pin "1") (pinfunction "1_1") (pintype "input"))
      (node (ref "FPC1") (pin "3") (pinfunction "3_3") (pintype "input"))
    )
    (net (code "27") (name "Net-(C37-Pad2)") (class "Default")
      (node (ref "C37") (pin "2") (pinfunction "2_2") (pintype "input"))
      (node (ref "FPC1") (pin "2") (pinfunction "2_2") (pintype "input"))
    )
    (net (code "28") (name "Net-(C38-Pad2)") (class "Default")
      (node (ref "C38") (pin "2") (pinfunction "2_2") (pintype "input"))
      (node (ref "FPC1") (pin "1") (pinfunction "1_1") (pintype "input"))
    )
    (net (code "29") (name "Net-(D1-C)") (class "Default")
      (node (ref "D1") (pin "1") (pinfunction "C_1") (pintype "input"))
      (node (ref "R1") (pin "1") (pinfunction "1_1") (pintype "input"))
      (node (ref "R11") (pin "2") (pinfunction "2_2") (pintype "input"))
      (node (ref "R12") (pin "1") (pinfunction "1_1") (pintype "input"))
      (node (ref "R4") (pin "1") (pinfunction "1_1") (pintype "input"))
      (node (ref "R5") (pin "1") (pinfunction "1_1") (pintype "input"))
    )
    (net (code "30") (name "Net-(H1-Pad1)") (class "Default")
      (node (ref "H1") (pin "1") (pinfunction "1_1") (pintype "unspecified"))
      (node (ref "U1") (pin "1") (pinfunction "1_1") (pintype "input"))
      (node (ref "U2") (pin "1") (pinfunction "1_1") (pintype "input"))
    )
    (net (code "31") (name "Net-(L1-Pad1)") (class "Default")
      (node (ref "L1") (pin "1") (pinfunction "1_1") (pintype "input"))
      (node (ref "L3") (pin "1") (pinfunction "1_1") (pintype "input"))
    )
    (net (code "32") (name "Net-(L1-Pad2)") (class "Default")
      (node (ref "L1") (pin "2") (pinfunction "2_2") (pintype "input"))
      (node (ref "L2") (pin "1") (pinfunction "1_1") (pintype "input"))
    )
    (net (code "33") (name "Net-(L2-Pad2)") (class "Default")
      (node (ref "L2") (pin "2") (pinfunction "2_2") (pintype "input"))
      (node (ref "L4") (pin "2") (pinfunction "2_2") (pintype "input"))
    )
    (net (code "34") (name "Net-(L3-Pad2)") (class "Default")
      (node (ref "L3") (pin "2") (pinfunction "2_2") (pintype "input"))
      (node (ref "L5") (pin "2") (pinfunction "2_2") (pintype "input"))
    )
    (net (code "35") (name "Net-(L4-Pad1)") (class "Default")
      (node (ref "L4") (pin "1") (pinfunction "1_1") (pintype "input"))
      (node (ref "L6") (pin "1") (pinfunction "1_1") (pintype "input"))
    )
    (net (code "36") (name "Net-(L5-Pad1)") (class "Default")
      (node (ref "L5") (pin "1") (pinfunction "1_1") (pintype "input"))
      (node (ref "L7") (pin "1") (pinfunction "1_1") (pintype "input"))
    )
    (net (code "37") (name "Net-(L6-Pad2)") (class "Default")
      (node (ref "L6") (pin "2") (pinfunction "2_2") (pintype "input"))
      (node (ref "L8") (pin "2") (pinfunction "2_2") (pintype "input"))
    )
    (net (code "38") (name "Net-(L7-Pad2)") (class "Default")
      (node (ref "L7") (pin "2") (pinfunction "2_2") (pintype "input"))
      (node (ref "L9") (pin "2") (pinfunction "2_2") (pintype "input"))
    )
    (net (code "39") (name "Net-(L9-Pad1)") (class "Default")
      (node (ref "L9") (pin "1") (pinfunction "1_1") (pintype "input"))
      (node (ref "U1") (pin "2") (pinfunction "2_2") (pintype "input"))
      (node (ref "U2") (pin "2") (pinfunction "2_2") (pintype "input"))
    )
    (net (code "40") (name "Net-(L10-Pad1)") (class "Default")
      (node (ref "L10") (pin "1") (pinfunction "1_1") (pintype "input"))
      (node (ref "L8") (pin "1") (pinfunction "1_1") (pintype "input"))
    )
    (net (code "41") (name "Net-(L10-Pad2)") (class "Default")
      (node (ref "L10") (pin "2") (pinfunction "2_2") (pintype "input"))
      (node (ref "R11") (pin "1") (pinfunction "1_1") (pintype "input"))
    )
    (net (code "42") (name "Net-(LED1-A)") (class "Default")
      (node (ref "C34") (pin "2") (pinfunction "2_2") (pintype "input"))
      (node (ref "LED1") (pin "1") (pinfunction "A_1") (pintype "input"))
      (node (ref "LED2") (pin "1") (pinfunction "A_1") (pintype "input"))
      (node (ref "U5") (pin "4") (pinfunction "Vcc_4") (pintype "input"))
      (node (ref "U5") (pin "8") (pinfunction "CE_8") (pintype "input"))
      (node (ref "USB1") (pin "11") (pinfunction "VBUS_11") (pintype "input"))
      (node (ref "USB1") (pin "2") (pinfunction "VBUS_2") (pintype "input"))
    )
    (net (code "43") (name "Net-(LED1-K)") (class "Default")
      (node (ref "LED1") (pin "2") (pinfunction "K_2") (pintype "input"))
      (node (ref "R42") (pin "2") (pinfunction "2_2") (pintype "input"))
    )
    (net (code "44") (name "Net-(LED2-K)") (class "Default")
      (node (ref "LED2") (pin "2") (pinfunction "K_2") (pintype "input"))
      (node (ref "R43") (pin "2") (pinfunction "2_2") (pintype "input"))
    )
    (net (code "45") (name "Net-(Q1-B)") (class "Default")
      (node (ref "Q1") (pin "1") (pinfunction "B_1") (pintype "input"))
      (node (ref "Q2") (pin "3") (pinfunction "C_3") (pintype "input"))
      (node (ref "R12") (pin "2") (pinfunction "2_2") (pintype "input"))
      (node (ref "R14") (pin "1") (pinfunction "1_1") (pintype "input"))
      (node (ref "R4") (pin "2") (pinfunction "2_2") (pintype "input"))
      (node (ref "R5") (pin "2") (pinfunction "2_2") (pintype "input"))
      (node (ref "U10") (pin "7") (pinfunction "OUT2_7") (pintype "output"))
    )
    (net (code "46") (name "Net-(Q3-B)") (class "Default")
      (node (ref "Q3") (pin "1") (pinfunction "B_1") (pintype "input"))
      (node (ref "Q4") (pin "3") (pinfunction "C_3") (pintype "input"))
      (node (ref "R18") (pin "2") (pinfunction "2_2") (pintype "input"))
      (node (ref "U11") (pin "3") (pinfunction "IN1+_3") (pintype "input"))
    )
    (net (code "47") (name "Net-(Q5-B)") (class "Default")
      (node (ref "Q5") (pin "1") (pinfunction "B_1") (pintype "input"))
      (node (ref "Q6") (pin "3") (pinfunction "C_3") (pintype "input"))
      (node (ref "R38") (pin "2") (pinfunction "2_2") (pintype "input"))
      (node (ref "U11") (pin "5") (pinfunction "IN2+_5") (pintype "input"))
    )
    (net (code "48") (name "Net-(R10-Pad1)") (class "Default")
      (node (ref "R10") (pin "1") (pinfunction "1_1") (pintype "input"))
      (node (ref "R15") (pin "2") (pinfunction "2_2") (pintype "input"))
      (node (ref "R16") (pin "2") (pinfunction "2_2") (pintype "input"))
      (node (ref "R9") (pin "2") (pinfunction "2_2") (pintype "input"))
    )
    (net (code "49") (name "Net-(R30-Pad1)") (class "Default")
      (node (ref "R30") (pin "1") (pinfunction "1_1") (pintype "input"))
      (node (ref "SW1") (pin "1") (pinfunction "1_1") (pintype "input"))
      (node (ref "SW1") (pin "2") (pinfunction "2_2") (pintype "input"))
    )
    (net (code "50") (name "Net-(R31-Pad1)") (class "Default")
      (node (ref "R31") (pin "1") (pinfunction "1_1") (pintype "input"))
      (node (ref "SW2") (pin "1") (pinfunction "1_1") (pintype "input"))
      (node (ref "SW2") (pin "2") (pinfunction "2_2") (pintype "input"))
    )
    (net (code "51") (name "Net-(R45-Pad1)") (class "Default")
      (node (ref "R45") (pin "1") (pinfunction "1_1") (pintype "input"))
      (node (ref "R46") (pin "2") (pinfunction "2_2") (pintype "input"))
      (node (ref "R48") (pin "1") (pinfunction "1_1") (pintype "input"))
    )
    (net (code "52") (name "Net-(U3-P108{slash}SWDIO)") (class "Default")
      (node (ref "H6") (pin "1") (pinfunction "1_1") (pintype "unspecified"))
      (node (ref "U3") (pin "25") (pinfunction "P108/SWDIO_25") (pintype "input"))
    )
    (net (code "53") (name "Net-(U3-P109)") (class "Default")
      (node (ref "R30") (pin "2") (pinfunction "2_2") (pintype "input"))
      (node (ref "U3") (pin "26") (pinfunction "P109_26") (pintype "input"))
    )
    (net (code "54") (name "Net-(U3-P110)") (class "Default")
      (node (ref "R31") (pin "2") (pinfunction "2_2") (pintype "input"))
      (node (ref "U3") (pin "27") (pinfunction "P110_27") (pintype "input"))
    )
    (net (code "55") (name "Net-(U3-P200)") (class "Default")
      (node (ref "R20") (pin "1") (pinfunction "1_1") (pintype "input"))
      (node (ref "U3") (pin "21") (pinfunction "P200_21") (pintype "input"))
    )
    (net (code "56") (name "Net-(U3-P201{slash}MD)") (class "Default")
      (node (ref "R21") (pin "1") (pinfunction "1_1") (pintype "input"))
      (node (ref "U3") (pin "20") (pinfunction "P201/MD_20") (pintype "input"))
    )
    (net (code "57") (name "Net-(U3-P212{slash}EXTAL)") (class "Default")
      (node (ref "C18") (pin "2") (pinfunction "2_2") (pintype "input"))
      (node (ref "U3") (pin "8") (pinfunction "P212/EXTAL_8") (pintype "input"))
      (node (ref "X1") (pin "1") (pinfunction "1_1") (pintype "input"))
    )
    (net (code "58") (name "Net-(U3-P213{slash}XTAL)") (class "Default")
      (node (ref "C19") (pin "2") (pinfunction "2_2") (pintype "input"))
      (node (ref "U3") (pin "7") (pinfunction "P213/XTAL_7") (pintype "input"))
      (node (ref "X1") (pin "3") (pinfunction "3_3") (pintype "input"))
    )
    (net (code "59") (name "Net-(U3-P300{slash}SWCLK)") (class "Default")
      (node (ref "H5") (pin "1") (pinfunction "1_1") (pintype "unspecified"))
      (node (ref "U3") (pin "24") (pinfunction "P300/SWCLK_24") (pintype "input"))
    )
    (net (code "60") (name "Net-(U3-RES)") (class "Default")
      (node (ref "C24") (pin "2") (pinfunction "2_2") (pintype "input"))
      (node (ref "R22") (pin "1") (pinfunction "1_1") (pintype "input"))
      (node (ref "U3") (pin "19") (pinfunction "RES_19") (pintype "input"))
    )
    (net (code "61") (name "Net-(U3-VCL)") (class "Default")
      (node (ref "C13") (pin "2") (pinfunction "2_2") (pintype "input"))
      (node (ref "U3") (pin "3") (pinfunction "VCL_3") (pintype "input"))
    )
    (net (code "62") (name "Net-(U4-A)") (class "Default")
      (node (ref "C29") (pin "2") (pinfunction "2_2") (pintype "input"))
      (node (ref "U4") (pin "4") (pinfunction "A_4") (pintype "input"))
    )
    (net (code "63") (name "Net-(U4-B0)") (class "Default")
      (node (ref "R26") (pin "1") (pinfunction "1_1") (pintype "input"))
      (node (ref "R27") (pin "1") (pinfunction "1_1") (pintype "input"))
      (node (ref "R29") (pin "2") (pinfunction "2_2") (pintype "input"))
      (node (ref "U4") (pin "3") (pinfunction "B0_3") (pintype "input"))
    )
    (net (code "64") (name "Net-(U5-CHRG#)") (class "Default")
      (node (ref "R42") (pin "1") (pinfunction "1_1") (pintype "input"))
      (node (ref "U5") (pin "7") (pinfunction "CHRG#_7") (pintype "input"))
    )
    (net (code "65") (name "Net-(U5-PROG)") (class "Default")
      (node (ref "R46") (pin "1") (pinfunction "1_1") (pintype "input"))
      (node (ref "U5") (pin "2") (pinfunction "PROG_2") (pintype "input"))
    )
    (net (code "66") (name "Net-(U5-STDBY#)") (class "Default")
      (node (ref "R43") (pin "1") (pinfunction "1_1") (pintype "input"))
      (node (ref "U5") (pin "6") (pinfunction "STDBY#_6") (pintype "input"))
    )
    (net (code "67") (name "Net-(U7-CS)") (class "Default")
      (node (ref "R54") (pin "2") (pinfunction "2_2") (pintype "input"))
      (node (ref "U7") (pin "2") (pinfunction "CS_2") (pintype "input"))
    )
    (net (code "68") (name "Net-(U7-OC)") (class "Default")
      (node (ref "U7") (pin "3") (pinfunction "OC_3") (pintype "input"))
      (node (ref "U9") (pin "1") (pinfunction "G_1") (pintype "input"))
    )
    (net (code "69") (name "Net-(U7-OD)") (class "Default")
      (node (ref "U7") (pin "1") (pinfunction "OD_1") (pintype "input"))
      (node (ref "U8") (pin "1") (pinfunction "G_1") (pintype "input"))
    )
    (net (code "70") (name "Net-(U7-VCC)") (class "Default")
      (node (ref "C42") (pin "2") (pinfunction "2_2") (pintype "input"))
      (node (ref "R49") (pin "1") (pinfunction "1_1") (pintype "input"))
      (node (ref "U7") (pin "5") (pinfunction "VCC_5") (pintype "input"))
    )
    (net (code "71") (name "Net-(U8-D)") (class "Default")
      (node (ref "U8") (pin "3") (pinfunction "D_3") (pintype "input"))
      (node (ref "U9") (pin "3") (pinfunction "D_3") (pintype "input"))
    )
    (net (code "72") (name "Net-(U10A-IN1+)") (class "Default")
      (node (ref "C7") (pin "1") (pinfunction "1_1") (pintype "input"))
      (node (ref "R13") (pin "2") (pinfunction "2_2") (pintype "input"))
      (node (ref "R3") (pin "1") (pinfunction "1_1") (pintype "input"))
      (node (ref "U10") (pin "3") (pinfunction "IN1+_3") (pintype "input"))
    )
    (net (code "73") (name "Net-(U10A-IN1-)") (class "Default")
      (node (ref "R2") (pin "1") (pinfunction "1_1") (pintype "input"))
      (node (ref "U10") (pin "1") (pinfunction "OUT_1") (pintype "output"))
      (node (ref "U10") (pin "2") (pinfunction "IN1-_2") (pintype "input"))
    )
    (net (code "74") (name "Net-(U10B-IN2+)") (class "Default")
      (node (ref "R1") (pin "2") (pinfunction "2_2") (pintype "input"))
      (node (ref "R2") (pin "2") (pinfunction "2_2") (pintype "input"))
      (node (ref "U10") (pin "5") (pinfunction "IN2+_5") (pintype "input"))
    )
    (net (code "75") (name "Net-(U10B-IN2-)") (class "Default")
      (node (ref "R14") (pin "2") (pinfunction "2_2") (pintype "input"))
      (node (ref "R17") (pin "2") (pinfunction "2_2") (pintype "input"))
      (node (ref "U10") (pin "6") (pinfunction "IN2-_6") (pintype "input"))
    )
    (net (code "76") (name "Net-(U11A-IN1-)") (class "Default")
      (node (ref "C26") (pin "2") (pinfunction "2_2") (pintype "input"))
      (node (ref "R25") (pin "1") (pinfunction "1_1") (pintype "input"))
      (node (ref "R28") (pin "2") (pinfunction "2_2") (pintype "input"))
      (node (ref "U11") (pin "2") (pinfunction "IN1-_2") (pintype "input"))
    )
    (net (code "77") (name "Net-(U11A-OUT)") (class "Default")
      (node (ref "C26") (pin "1") (pinfunction "1_1") (pintype "input"))
      (node (ref "R23") (pin "1") (pinfunction "1_1") (pintype "input"))
      (node (ref "R25") (pin "2") (pinfunction "2_2") (pintype "input"))
      (node (ref "U11") (pin "1") (pinfunction "OUT_1") (pintype "output"))
    )
    (net (code "78") (name "Net-(U11B-IN2-)") (class "Default")
      (node (ref "C27") (pin "2") (pinfunction "2_2") (pintype "input"))
      (node (ref "R28") (pin "1") (pinfunction "1_1") (pintype "input"))
      (node (ref "R32") (pin "1") (pinfunction "1_1") (pintype "input"))
      (node (ref "U11") (pin "6") (pinfunction "IN2-_6") (pintype "input"))
    )
    (net (code "79") (name "Net-(U11B-OUT2)") (class "Default")
      (node (ref "C27") (pin "1") (pinfunction "1_1") (pintype "input"))
      (node (ref "R32") (pin "2") (pinfunction "2_2") (pintype "input"))
      (node (ref "R33") (pin "1") (pinfunction "1_1") (pintype "input"))
      (node (ref "U11") (pin "7") (pinfunction "OUT2_7") (pintype "output"))
    )
    (net (code "80") (name "Net-(U12A-IN1+)") (class "Default")
      (node (ref "C20") (pin "2") (pinfunction "2_2") (pintype "input"))
      (node (ref "R23") (pin "2") (pinfunction "2_2") (pintype "input"))
      (node (ref "R24") (pin "1") (pinfunction "1_1") (pintype "input"))
      (node (ref "U12") (pin "3") (pinfunction "IN1+_3") (pintype "input"))
    )
    (net (code "81") (name "Net-(U12A-IN1-)") (class "Default")
      (node (ref "C30") (pin "2") (pinfunction "2_2") (pintype "input"))
      (node (ref "R33") (pin "2") (pinfunction "2_2") (pintype "input"))
      (node (ref "R34") (pin "1") (pinfunction "1_1") (pintype "input"))
      (node (ref "U12") (pin "2") (pinfunction "IN1-_2") (pintype "input"))
    )
    (net (code "82") (name "Net-(U12A-OUT)") (class "Default")
      (node (ref "C30") (pin "1") (pinfunction "1_1") (pintype "input"))
      (node (ref "R26") (pin "2") (pinfunction "2_2") (pintype "input"))
      (node (ref "R27") (pin "2") (pinfunction "2_2") (pintype "input"))
      (node (ref "R34") (pin "2") (pinfunction "2_2") (pintype "input"))
      (node (ref "U12") (pin "1") (pinfunction "OUT_1") (pintype "output"))
      (node (ref "U4") (pin "1") (pinfunction "B1_1") (pintype "input"))
    )
    (net (code "83") (name "Net-(U12B-IN2+)") (class "Default")
      (node (ref "C29") (pin "1") (pinfunction "1_1") (pintype "input"))
      (node (ref "R35") (pin "1") (pinfunction "1_1") (pintype "input"))
      (node (ref "R36") (pin "2") (pinfunction "2_2") (pintype "input"))
      (node (ref "U12") (pin "5") (pinfunction "IN2+_5") (pintype "input"))
    )
    (net (code "84") (name "Net-(U12B-IN2-)") (class "Default")
      (node (ref "C33") (pin "2") (pinfunction "2_2") (pintype "input"))
      (node (ref "R39") (pin "1") (pinfunction "1_1") (pintype "input"))
      (node (ref "R40") (pin "2") (pinfunction "2_2") (pintype "input"))
      (node (ref "R41") (pin "1") (pinfunction "1_1") (pintype "input"))
      (node (ref "U12") (pin "6") (pinfunction "IN2-_6") (pintype "input"))
    )
    (net (code "85") (name "Net-(USB1-CC1)") (class "Default")
      (node (ref "R47") (pin "1") (pinfunction "1_1") (pintype "input"))
      (node (ref "USB1") (pin "4") (pinfunction "CC1_4") (pintype "input"))
    )
    (net (code "86") (name "Net-(USB1-CC2)") (class "Default")
      (node (ref "R44") (pin "1") (pinfunction "1_1") (pintype "input"))
      (node (ref "USB1") (pin "10") (pinfunction "CC2_10") (pintype "input"))
    )
    (net (code "87") (name "VCC") (class "Default")
      (node (ref "C1") (pin "2") (pinfunction "2_2") (pintype "input"))
      (node (ref "C2") (pin "2") (pinfunction "2_2") (pintype "input"))
      (node (ref "C39") (pin "2") (pinfunction "2_2") (pintype "input"))
      (node (ref "Q1") (pin "3") (pinfunction "C_3") (pintype "input"))
      (node (ref "R3") (pin "2") (pinfunction "2_2") (pintype "input"))
      (node (ref "SW3") (pin "3") (pinfunction "3_3") (pintype "input"))
      (node (ref "U10") (pin "8") (pinfunction "VCC_8") (pintype "input"))
      (node (ref "U6") (pin "3") (pinfunction "VIN_3") (pintype "input"))
    )
    (net (code "88") (name "unconnected-(Q1-E-Pad2)") (class "Default")
      (node (ref "Q1") (pin "2") (pinfunction "E_2") (pintype "input+no_connect"))
    )
    (net (code "89") (name "unconnected-(Q2-E-Pad2)") (class "Default")
      (node (ref "Q2") (pin "2") (pinfunction "E_2") (pintype "input+no_connect"))
    )
    (net (code "90") (name "unconnected-(Q3-E-Pad2)") (class "Default")
      (node (ref "Q3") (pin "2") (pinfunction "E_2") (pintype "input+no_connect"))
    )
    (net (code "91") (name "unconnected-(Q4-E-Pad2)") (class "Default")
      (node (ref "Q4") (pin "2") (pinfunction "E_2") (pintype "input+no_connect"))
    )
    (net (code "92") (name "unconnected-(Q5-E-Pad2)") (class "Default")
      (node (ref "Q5") (pin "2") (pinfunction "E_2") (pintype "input+no_connect"))
    )
    (net (code "93") (name "unconnected-(Q6-E-Pad2)") (class "Default")
      (node (ref "Q6") (pin "2") (pinfunction "E_2") (pintype "input+no_connect"))
    )
    (net (code "94") (name "unconnected-(TP1-Pad1)") (class "Default")
      (node (ref "TP1") (pin "1") (pinfunction "1_1") (pintype "input"))
    )
    (net (code "95") (name "unconnected-(TP2-Pad1)") (class "Default")
      (node (ref "TP2") (pin "1") (pinfunction "1_1") (pintype "input"))
    )
    (net (code "96") (name "unconnected-(TP3-Pad1)") (class "Default")
      (node (ref "TP3") (pin "1") (pinfunction "1_1") (pintype "input"))
    )
    (net (code "97") (name "unconnected-(TP4-Pad1)") (class "Default")
      (node (ref "TP4") (pin "1") (pinfunction "1_1") (pintype "input"))
    )
    (net (code "98") (name "unconnected-(U3-P000-Pad48)") (class "Default")
      (node (ref "U3") (pin "48") (pinfunction "P000_48") (pintype "input"))
    )
    (net (code "99") (name "unconnected-(U3-P002-Pad46)") (class "Default")
      (node (ref "U3") (pin "46") (pinfunction "P002_46") (pintype "input"))
    )
    (net (code "100") (name "unconnected-(U3-P012-Pad41)") (class "Default")
      (node (ref "U3") (pin "41") (pinfunction "P012_41") (pintype "input"))
    )
    (net (code "101") (name "unconnected-(U3-P013-Pad40)") (class "Default")
      (node (ref "U3") (pin "40") (pinfunction "P013_40") (pintype "input"))
    )
    (net (code "102") (name "unconnected-(U3-P014-Pad39)") (class "Default")
      (node (ref "U3") (pin "39") (pinfunction "P014_39") (pintype "input"))
    )
    (net (code "103") (name "unconnected-(U3-P100-Pad36)") (class "Default")
      (node (ref "U3") (pin "36") (pinfunction "P100_36") (pintype "input"))
    )
    (net (code "104") (name "unconnected-(U3-P104-Pad32)") (class "Default")
      (node (ref "U3") (pin "32") (pinfunction "P104_32") (pintype "input"))
    )
    (net (code "105") (name "unconnected-(U3-P111-Pad28)") (class "Default")
      (node (ref "U3") (pin "28") (pinfunction "P111_28") (pintype "input"))
    )
    (net (code "106") (name "unconnected-(U3-P112-Pad29)") (class "Default")
      (node (ref "U3") (pin "29") (pinfunction "P112_29") (pintype "input"))
    )
    (net (code "107") (name "unconnected-(U3-P206-Pad18)") (class "Default")
      (node (ref "U3") (pin "18") (pinfunction "P206_18") (pintype "input"))
    )
    (net (code "108") (name "unconnected-(U3-P207-Pad17)") (class "Default")
      (node (ref "U3") (pin "17") (pinfunction "P207_17") (pintype "input"))
    )
    (net (code "109") (name "unconnected-(U3-P208-Pad16)") (class "Default")
      (node (ref "U3") (pin "16") (pinfunction "P208_16") (pintype "input"))
    )
    (net (code "110") (name "unconnected-(U3-P214{slash}XCOUT-Pad5)") (class "Default")
      (node (ref "U3") (pin "5") (pinfunction "P214/XCOUT_5") (pintype "input"))
    )
    (net (code "111") (name "unconnected-(U3-P215{slash}XCIN-Pad4)") (class "Default")
      (node (ref "U3") (pin "4") (pinfunction "P215/XCIN_4") (pintype "input"))
    )
    (net (code "112") (name "unconnected-(U3-P301-Pad23)") (class "Default")
      (node (ref "U3") (pin "23") (pinfunction "P301_23") (pintype "input"))
    )
    (net (code "113") (name "unconnected-(U3-P302-Pad22)") (class "Default")
      (node (ref "U3") (pin "22") (pinfunction "P302_22") (pintype "input"))
    )
    (net (code "114") (name "unconnected-(U3-P407-Pad12)") (class "Default")
      (node (ref "U3") (pin "12") (pinfunction "P407_12") (pintype "input"))
    )
    (net (code "115") (name "unconnected-(U3-P408-Pad11)") (class "Default")
      (node (ref "U3") (pin "11") (pinfunction "P408_11") (pintype "input"))
    )
    (net (code "116") (name "unconnected-(U3-P409-Pad10)") (class "Default")
      (node (ref "U3") (pin "10") (pinfunction "P409_10") (pintype "input"))
    )
    (net (code "117") (name "unconnected-(U3-P913-Pad15)") (class "Default")
      (node (ref "U3") (pin "15") (pinfunction "P913_15") (pintype "input"))
    )
    (net (code "118") (name "unconnected-(U3-P914-Pad14)") (class "Default")
      (node (ref "U3") (pin "14") (pinfunction "P914_14") (pintype "input"))
    )
    (net (code "119") (name "unconnected-(U3-P915-Pad13)") (class "Default")
      (node (ref "U3") (pin "13") (pinfunction "P915_13") (pintype "input"))
    )
    (net (code "120") (name "unconnected-(U7-TD-Pad4)") (class "Default")
      (node (ref "U7") (pin "4") (pinfunction "TD_4") (pintype "input"))
    )
    (net (code "121") (name "unconnected-(USB1-DN1-Pad7)") (class "Default")
      (node (ref "USB1") (pin "7") (pinfunction "DN1_7") (pintype "input"))
    )
    (net (code "122") (name "unconnected-(USB1-DN2-Pad5)") (class "Default")
      (node (ref "USB1") (pin "5") (pinfunction "DN2_5") (pintype "input"))
    )
    (net (code "123") (name "unconnected-(USB1-DP1-Pad6)") (class "Default")
      (node (ref "USB1") (pin "6") (pinfunction "DP1_6") (pintype "input"))
    )
    (net (code "124") (name "unconnected-(USB1-DP2-Pad8)") (class "Default")
      (node (ref "USB1") (pin "8") (pinfunction "DP2_8") (pintype "input"))
    )
    (net (code "125") (name "unconnected-(USB1-SBU1-Pad9)") (class "Default")
      (node (ref "USB1") (pin "9") (pinfunction "SBU1_9") (pintype "input"))
    )
    (net (code "126") (name "unconnected-(USB1-SBU2-Pad3)") (class "Default")
      (node (ref "USB1") (pin "3") (pinfunction "SBU2_3") (pintype "input"))
    )
  )
)
